# HFPB_01_PAGE-2.net
KiCad netlist of a schematic drawn in Altium Designer
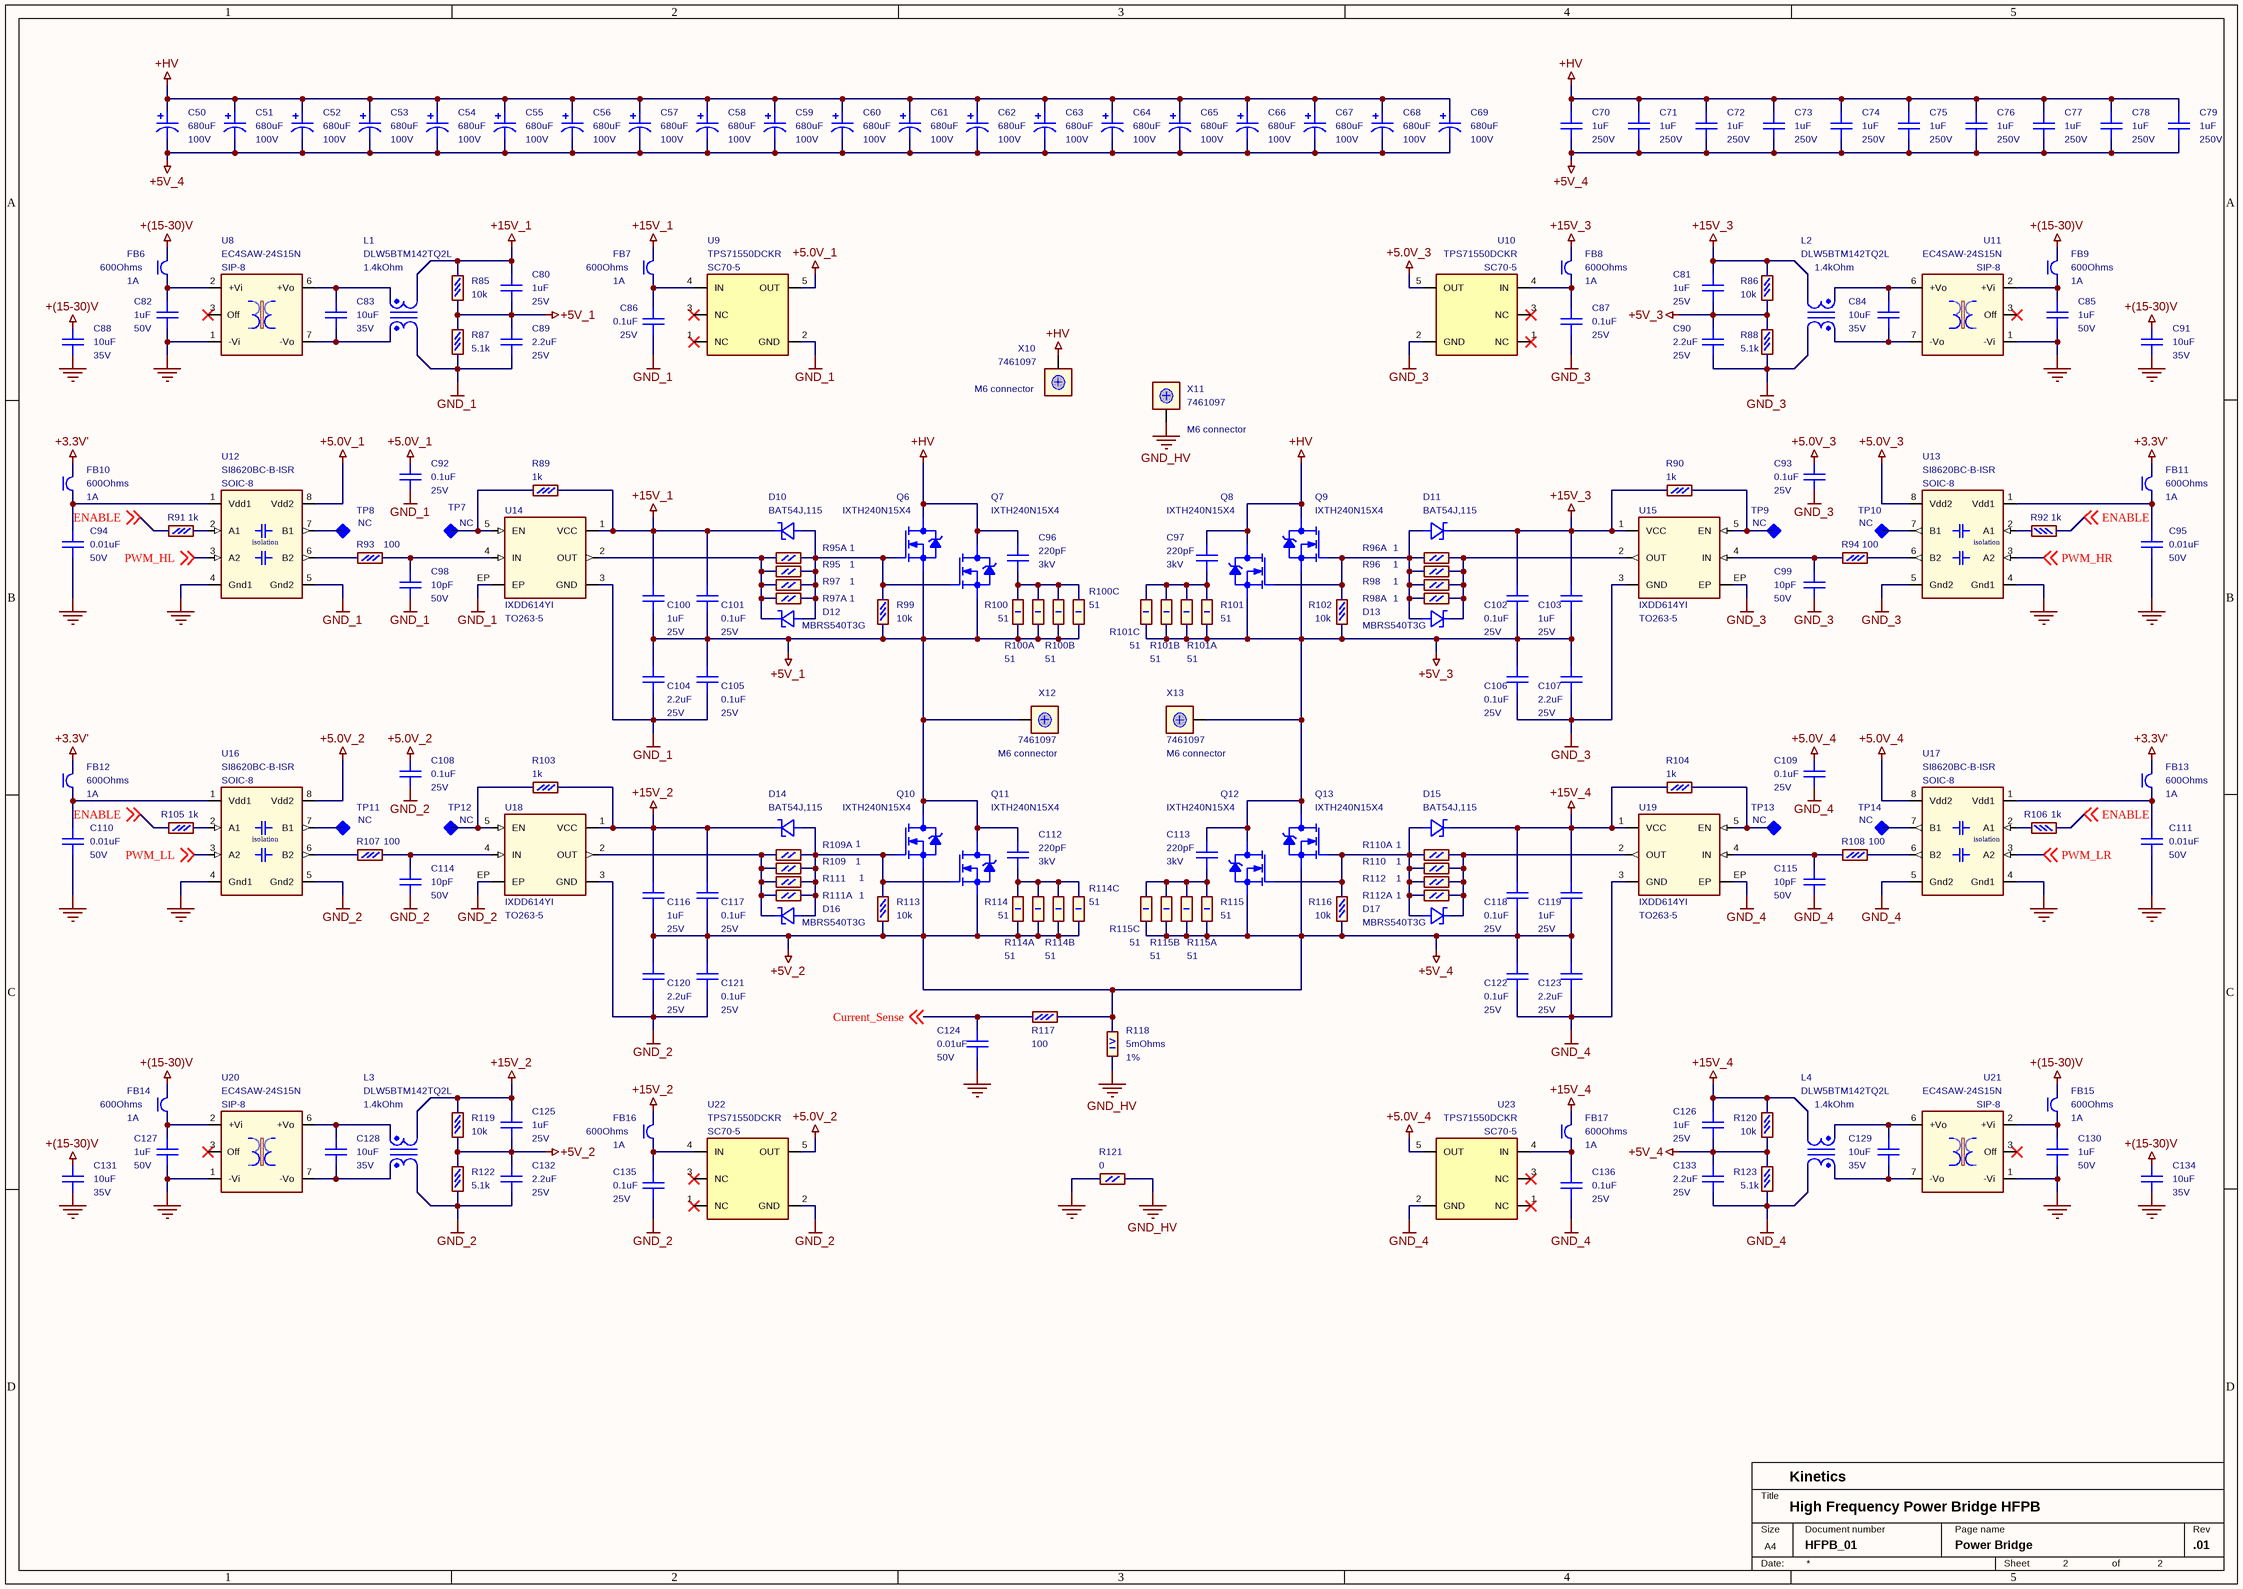
[diagram p0: HFPB_01, PAGE-2.SchDoc]

(export (version "E")
  (design (tool "Eeschema 10.0.6"))
  (components
    (comp (ref "C50")
      (value "680uF")
      (footprint "CAPPRD750W80D1820H4200")
      (description "Capacitor Aluminum Electrolytic Radial 680µF 100V 36mOhm")
      (fields
        (field (name "PART NUMBER") "EEU-FC2A681")
        (field (name "MANUFACTURER") "Panasonic")
        (field (name "VALUE3") "100V")
      )
      (libsource (lib "HFPB_01-SchLib") (part "EEU-FC2A681"))
    )
    (comp (ref "C51")
      (value "680uF")
      (footprint "CAPPRD750W80D1820H4200")
      (description "Capacitor Aluminum Electrolytic Radial 680µF 100V 36mOhm")
      (fields
        (field (name "PART NUMBER") "EEU-FC2A681")
        (field (name "MANUFACTURER") "Panasonic")
        (field (name "VALUE3") "100V")
      )
      (libsource (lib "HFPB_01-SchLib") (part "EEU-FC2A681"))
    )
    (comp (ref "C52")
      (value "680uF")
      (footprint "CAPPRD750W80D1820H4200")
      (description "Capacitor Aluminum Electrolytic Radial 680µF 100V 36mOhm")
      (fields
        (field (name "PART NUMBER") "EEU-FC2A681")
        (field (name "MANUFACTURER") "Panasonic")
        (field (name "VALUE3") "100V")
      )
      (libsource (lib "HFPB_01-SchLib") (part "EEU-FC2A681"))
    )
    (comp (ref "C53")
      (value "680uF")
      (footprint "CAPPRD750W80D1820H4200")
      (description "Capacitor Aluminum Electrolytic Radial 680µF 100V 36mOhm")
      (fields
        (field (name "PART NUMBER") "EEU-FC2A681")
        (field (name "MANUFACTURER") "Panasonic")
        (field (name "VALUE3") "100V")
      )
      (libsource (lib "HFPB_01-SchLib") (part "EEU-FC2A681"))
    )
    (comp (ref "C54")
      (value "680uF")
      (footprint "CAPPRD750W80D1820H4200")
      (description "Capacitor Aluminum Electrolytic Radial 680µF 100V 36mOhm")
      (fields
        (field (name "PART NUMBER") "EEU-FC2A681")
        (field (name "MANUFACTURER") "Panasonic")
        (field (name "VALUE3") "100V")
      )
      (libsource (lib "HFPB_01-SchLib") (part "EEU-FC2A681"))
    )
    (comp (ref "C55")
      (value "680uF")
      (footprint "CAPPRD750W80D1820H4200")
      (description "Capacitor Aluminum Electrolytic Radial 680µF 100V 36mOhm")
      (fields
        (field (name "PART NUMBER") "EEU-FC2A681")
        (field (name "MANUFACTURER") "Panasonic")
        (field (name "VALUE3") "100V")
      )
      (libsource (lib "HFPB_01-SchLib") (part "EEU-FC2A681"))
    )
    (comp (ref "C56")
      (value "680uF")
      (footprint "CAPPRD750W80D1820H4200")
      (description "Capacitor Aluminum Electrolytic Radial 680µF 100V 36mOhm")
      (fields
        (field (name "PART NUMBER") "EEU-FC2A681")
        (field (name "MANUFACTURER") "Panasonic")
        (field (name "VALUE3") "100V")
      )
      (libsource (lib "HFPB_01-SchLib") (part "EEU-FC2A681"))
    )
    (comp (ref "C57")
      (value "680uF")
      (footprint "CAPPRD750W80D1820H4200")
      (description "Capacitor Aluminum Electrolytic Radial 680µF 100V 36mOhm")
      (fields
        (field (name "PART NUMBER") "EEU-FC2A681")
        (field (name "MANUFACTURER") "Panasonic")
        (field (name "VALUE3") "100V")
      )
      (libsource (lib "HFPB_01-SchLib") (part "EEU-FC2A681"))
    )
    (comp (ref "C58")
      (value "680uF")
      (footprint "CAPPRD750W80D1820H4200")
      (description "Capacitor Aluminum Electrolytic Radial 680µF 100V 36mOhm")
      (fields
        (field (name "PART NUMBER") "EEU-FC2A681")
        (field (name "MANUFACTURER") "Panasonic")
        (field (name "VALUE3") "100V")
      )
      (libsource (lib "HFPB_01-SchLib") (part "EEU-FC2A681"))
    )
    (comp (ref "C59")
      (value "680uF")
      (footprint "CAPPRD750W80D1820H4200")
      (description "Capacitor Aluminum Electrolytic Radial 680µF 100V 36mOhm")
      (fields
        (field (name "PART NUMBER") "EEU-FC2A681")
        (field (name "MANUFACTURER") "Panasonic")
        (field (name "VALUE3") "100V")
      )
      (libsource (lib "HFPB_01-SchLib") (part "EEU-FC2A681"))
    )
    (comp (ref "C60")
      (value "680uF")
      (footprint "CAPPRD750W80D1820H4200")
      (description "Capacitor Aluminum Electrolytic Radial 680µF 100V 36mOhm")
      (fields
        (field (name "PART NUMBER") "EEU-FC2A681")
        (field (name "MANUFACTURER") "Panasonic")
        (field (name "VALUE3") "100V")
      )
      (libsource (lib "HFPB_01-SchLib") (part "EEU-FC2A681"))
    )
    (comp (ref "C61")
      (value "680uF")
      (footprint "CAPPRD750W80D1820H4200")
      (description "Capacitor Aluminum Electrolytic Radial 680µF 100V 36mOhm")
      (fields
        (field (name "PART NUMBER") "EEU-FC2A681")
        (field (name "MANUFACTURER") "Panasonic")
        (field (name "VALUE3") "100V")
      )
      (libsource (lib "HFPB_01-SchLib") (part "EEU-FC2A681"))
    )
    (comp (ref "C62")
      (value "680uF")
      (footprint "CAPPRD750W80D1820H4200")
      (description "Capacitor Aluminum Electrolytic Radial 680µF 100V 36mOhm")
      (fields
        (field (name "PART NUMBER") "EEU-FC2A681")
        (field (name "MANUFACTURER") "Panasonic")
        (field (name "VALUE3") "100V")
      )
      (libsource (lib "HFPB_01-SchLib") (part "EEU-FC2A681"))
    )
    (comp (ref "C63")
      (value "680uF")
      (footprint "CAPPRD750W80D1820H4200")
      (description "Capacitor Aluminum Electrolytic Radial 680µF 100V 36mOhm")
      (fields
        (field (name "PART NUMBER") "EEU-FC2A681")
        (field (name "MANUFACTURER") "Panasonic")
        (field (name "VALUE3") "100V")
      )
      (libsource (lib "HFPB_01-SchLib") (part "EEU-FC2A681"))
    )
    (comp (ref "C64")
      (value "680uF")
      (footprint "CAPPRD750W80D1820H4200")
      (description "Capacitor Aluminum Electrolytic Radial 680µF 100V 36mOhm")
      (fields
        (field (name "PART NUMBER") "EEU-FC2A681")
        (field (name "MANUFACTURER") "Panasonic")
        (field (name "VALUE3") "100V")
      )
      (libsource (lib "HFPB_01-SchLib") (part "EEU-FC2A681"))
    )
    (comp (ref "C65")
      (value "680uF")
      (footprint "CAPPRD750W80D1820H4200")
      (description "Capacitor Aluminum Electrolytic Radial 680µF 100V 36mOhm")
      (fields
        (field (name "PART NUMBER") "EEU-FC2A681")
        (field (name "MANUFACTURER") "Panasonic")
        (field (name "VALUE3") "100V")
      )
      (libsource (lib "HFPB_01-SchLib") (part "EEU-FC2A681"))
    )
    (comp (ref "C66")
      (value "680uF")
      (footprint "CAPPRD750W80D1820H4200")
      (description "Capacitor Aluminum Electrolytic Radial 680µF 100V 36mOhm")
      (fields
        (field (name "PART NUMBER") "EEU-FC2A681")
        (field (name "MANUFACTURER") "Panasonic")
        (field (name "VALUE3") "100V")
      )
      (libsource (lib "HFPB_01-SchLib") (part "EEU-FC2A681"))
    )
    (comp (ref "C67")
      (value "680uF")
      (footprint "CAPPRD750W80D1820H4200")
      (description "Capacitor Aluminum Electrolytic Radial 680µF 100V 36mOhm")
      (fields
        (field (name "PART NUMBER") "EEU-FC2A681")
        (field (name "MANUFACTURER") "Panasonic")
        (field (name "VALUE3") "100V")
      )
      (libsource (lib "HFPB_01-SchLib") (part "EEU-FC2A681"))
    )
    (comp (ref "C68")
      (value "680uF")
      (footprint "CAPPRD750W80D1820H4200")
      (description "Capacitor Aluminum Electrolytic Radial 680µF 100V 36mOhm")
      (fields
        (field (name "PART NUMBER") "EEU-FC2A681")
        (field (name "MANUFACTURER") "Panasonic")
        (field (name "VALUE3") "100V")
      )
      (libsource (lib "HFPB_01-SchLib") (part "EEU-FC2A681"))
    )
    (comp (ref "C69")
      (value "680uF")
      (footprint "CAPPRD750W80D1820H4200")
      (description "Capacitor Aluminum Electrolytic Radial 680µF 100V 36mOhm")
      (fields
        (field (name "PART NUMBER") "EEU-FC2A681")
        (field (name "MANUFACTURER") "Panasonic")
        (field (name "VALUE3") "100V")
      )
      (libsource (lib "HFPB_01-SchLib") (part "EEU-FC2A681"))
    )
    (comp (ref "C70")
      (value "1uF")
      (footprint "CAPC570X500X160L60N")
      (description "Capacitor 2220")
      (fields
        (field (name "PART NUMBER") "C2220C105KARACTU")
        (field (name "MANUFACTURER") "KEMET")
        (field (name "VALUE3") "250V")
      )
      (libsource (lib "HFPB_01-SchLib") (part "C2220"))
    )
    (comp (ref "C71")
      (value "1uF")
      (footprint "CAPC570X500X160L60N")
      (description "Capacitor 2220")
      (fields
        (field (name "PART NUMBER") "C2220C105KARACTU")
        (field (name "MANUFACTURER") "KEMET")
        (field (name "VALUE3") "250V")
      )
      (libsource (lib "HFPB_01-SchLib") (part "C2220"))
    )
    (comp (ref "C72")
      (value "1uF")
      (footprint "CAPC570X500X160L60N")
      (description "Capacitor 2220")
      (fields
        (field (name "PART NUMBER") "C2220C105KARACTU")
        (field (name "MANUFACTURER") "KEMET")
        (field (name "VALUE3") "250V")
      )
      (libsource (lib "HFPB_01-SchLib") (part "C2220"))
    )
    (comp (ref "C73")
      (value "1uF")
      (footprint "CAPC570X500X160L60N")
      (description "Capacitor 2220")
      (fields
        (field (name "PART NUMBER") "C2220C105KARACTU")
        (field (name "MANUFACTURER") "KEMET")
        (field (name "VALUE3") "250V")
      )
      (libsource (lib "HFPB_01-SchLib") (part "C2220"))
    )
    (comp (ref "C74")
      (value "1uF")
      (footprint "CAPC570X500X160L60N")
      (description "Capacitor 2220")
      (fields
        (field (name "PART NUMBER") "C2220C105KARACTU")
        (field (name "MANUFACTURER") "KEMET")
        (field (name "VALUE3") "250V")
      )
      (libsource (lib "HFPB_01-SchLib") (part "C2220"))
    )
    (comp (ref "C75")
      (value "1uF")
      (footprint "CAPC570X500X160L60N")
      (description "Capacitor 2220")
      (fields
        (field (name "PART NUMBER") "C2220C105KARACTU")
        (field (name "MANUFACTURER") "KEMET")
        (field (name "VALUE3") "250V")
      )
      (libsource (lib "HFPB_01-SchLib") (part "C2220"))
    )
    (comp (ref "C76")
      (value "1uF")
      (footprint "CAPC570X500X160L60N")
      (description "Capacitor 2220")
      (fields
        (field (name "PART NUMBER") "C2220C105KARACTU")
        (field (name "MANUFACTURER") "KEMET")
        (field (name "VALUE3") "250V")
      )
      (libsource (lib "HFPB_01-SchLib") (part "C2220"))
    )
    (comp (ref "C77")
      (value "1uF")
      (footprint "CAPC570X500X160L60N")
      (description "Capacitor 2220")
      (fields
        (field (name "PART NUMBER") "C2220C105KARACTU")
        (field (name "MANUFACTURER") "KEMET")
        (field (name "VALUE3") "250V")
      )
      (libsource (lib "HFPB_01-SchLib") (part "C2220"))
    )
    (comp (ref "C78")
      (value "1uF")
      (footprint "CAPC570X500X160L60N")
      (description "Capacitor 2220")
      (fields
        (field (name "PART NUMBER") "C2220C105KARACTU")
        (field (name "MANUFACTURER") "KEMET")
        (field (name "VALUE3") "250V")
      )
      (libsource (lib "HFPB_01-SchLib") (part "C2220"))
    )
    (comp (ref "C79")
      (value "1uF")
      (footprint "CAPC570X500X160L60N")
      (description "Capacitor 2220")
      (fields
        (field (name "PART NUMBER") "C2220C105KARACTU")
        (field (name "MANUFACTURER") "KEMET")
        (field (name "VALUE3") "250V")
      )
      (libsource (lib "HFPB_01-SchLib") (part "C2220"))
    )
    (comp (ref "C80")
      (value "1uF")
      (footprint "CAPC160X80X80L35N - Full legend")
      (description "Capacitor 0603")
      (fields
        (field (name "PART NUMBER") "C1608X7R1E105K080AB")
        (field (name "MANUFACTURER") "TDK")
        (field (name "VALUE3") "25V")
      )
      (libsource (lib "HFPB_01-SchLib") (part "C0603"))
    )
    (comp (ref "C81")
      (value "1uF")
      (footprint "CAPC160X80X80L35N - Full legend")
      (description "Capacitor 0603")
      (fields
        (field (name "PART NUMBER") "C1608X7R1E105K080AB")
        (field (name "MANUFACTURER") "TDK")
        (field (name "VALUE3") "25V")
      )
      (libsource (lib "HFPB_01-SchLib") (part "C0603"))
    )
    (comp (ref "C82")
      (value "1uF")
      (footprint "CAPC160X80X80L35N - Full legend")
      (description "Capacitor 0603")
      (fields
        (field (name "PART NUMBER") "GRT188R61H105KE13D")
        (field (name "MANUFACTURER") "Murata")
        (field (name "VALUE3") "50V")
      )
      (libsource (lib "HFPB_01-SchLib") (part "C0603"))
    )
    (comp (ref "C83")
      (value "10uF")
      (footprint "CAPC320X250X280L60N - full legend")
      (description "Capacitor 1210")
      (fields
        (field (name "PART NUMBER") "C1210C106M6PACTU")
        (field (name "MANUFACTURER") "KEMET")
        (field (name "VALUE3") "35V")
      )
      (libsource (lib "HFPB_01-SchLib") (part "C1210"))
    )
    (comp (ref "C84")
      (value "10uF")
      (footprint "CAPC320X250X280L60N - full legend")
      (description "Capacitor 1210")
      (fields
        (field (name "PART NUMBER") "C1210C106M6PACTU")
        (field (name "MANUFACTURER") "KEMET")
        (field (name "VALUE3") "35V")
      )
      (libsource (lib "HFPB_01-SchLib") (part "C1210"))
    )
    (comp (ref "C85")
      (value "1uF")
      (footprint "CAPC160X80X80L35N - Full legend")
      (description "Capacitor 0603")
      (fields
        (field (name "PART NUMBER") "GRT188R61H105KE13D")
        (field (name "MANUFACTURER") "Murata")
        (field (name "VALUE3") "50V")
      )
      (libsource (lib "HFPB_01-SchLib") (part "C0603"))
    )
    (comp (ref "C86")
      (value "0.1uF")
      (footprint "CAPC160X80X80L35N - Full legend")
      (description "Capacitor 0603")
      (fields
        (field (name "PART NUMBER") "C0603C104K3RAC7082")
        (field (name "MANUFACTURER") "KEMET")
        (field (name "VALUE3") "25V")
      )
      (libsource (lib "HFPB_01-SchLib") (part "C0603"))
    )
    (comp (ref "C87")
      (value "0.1uF")
      (footprint "CAPC160X80X80L35N - Full legend")
      (description "Capacitor 0603")
      (fields
        (field (name "PART NUMBER") "C0603C104K3RAC7082")
        (field (name "MANUFACTURER") "KEMET")
        (field (name "VALUE3") "25V")
      )
      (libsource (lib "HFPB_01-SchLib") (part "C0603"))
    )
    (comp (ref "C88")
      (value "10uF")
      (footprint "CAPC320X250X280L60N - full legend")
      (description "Capacitor 1210")
      (fields
        (field (name "PART NUMBER") "C1210C106M6PACTU")
        (field (name "MANUFACTURER") "KEMET")
        (field (name "VALUE3") "35V")
      )
      (libsource (lib "HFPB_01-SchLib") (part "C1210"))
    )
    (comp (ref "C89")
      (value "2.2uF")
      (footprint "CAPC160X80X80L35N - Full legend")
      (description "Capacitor 0603")
      (fields
        (field (name "PART NUMBER") "C1608X5R1E225K080AB")
        (field (name "MANUFACTURER") "TDK")
        (field (name "VALUE3") "25V")
      )
      (libsource (lib "HFPB_01-SchLib") (part "C0603"))
    )
    (comp (ref "C90")
      (value "2.2uF")
      (footprint "CAPC160X80X80L35N - Full legend")
      (description "Capacitor 0603")
      (fields
        (field (name "PART NUMBER") "C1608X5R1E225K080AB")
        (field (name "MANUFACTURER") "TDK")
        (field (name "VALUE3") "25V")
      )
      (libsource (lib "HFPB_01-SchLib") (part "C0603"))
    )
    (comp (ref "C91")
      (value "10uF")
      (footprint "CAPC320X250X280L60N - full legend")
      (description "Capacitor 1210")
      (fields
        (field (name "PART NUMBER") "C1210C106M6PACTU")
        (field (name "MANUFACTURER") "KEMET")
        (field (name "VALUE3") "35V")
      )
      (libsource (lib "HFPB_01-SchLib") (part "C1210"))
    )
    (comp (ref "C92")
      (value "0.1uF")
      (footprint "CAPC160X80X80L35N - Full legend")
      (description "Capacitor 0603")
      (fields
        (field (name "PART NUMBER") "C0603C104K3RAC7082")
        (field (name "MANUFACTURER") "KEMET")
        (field (name "VALUE3") "25V")
      )
      (libsource (lib "HFPB_01-SchLib") (part "C0603"))
    )
    (comp (ref "C93")
      (value "0.1uF")
      (footprint "CAPC160X80X80L35N - Full legend")
      (description "Capacitor 0603")
      (fields
        (field (name "PART NUMBER") "C0603C104K3RAC7082")
        (field (name "MANUFACTURER") "KEMET")
        (field (name "VALUE3") "25V")
      )
      (libsource (lib "HFPB_01-SchLib") (part "C0603"))
    )
    (comp (ref "C94")
      (value "0.01uF")
      (footprint "CAPC160X80X80L35N - Full legend")
      (description "Capacitor 0603")
      (fields
        (field (name "PART NUMBER") "GRM1885C1H103JA01D")
        (field (name "MANUFACTURER") "Murata")
        (field (name "VALUE3") "50V")
      )
      (libsource (lib "HFPB_01-SchLib") (part "C0603"))
    )
    (comp (ref "C95")
      (value "0.01uF")
      (footprint "CAPC160X80X80L35N - Full legend")
      (description "Capacitor 0603")
      (fields
        (field (name "PART NUMBER") "GRM1885C1H103JA01D")
        (field (name "MANUFACTURER") "Murata")
        (field (name "VALUE3") "50V")
      )
      (libsource (lib "HFPB_01-SchLib") (part "C0603"))
    )
    (comp (ref "C96")
      (value "220pF")
      (footprint "CAPC450X320X140L60N")
      (description "Capacitor 1812")
      (fields
        (field (name "PART NUMBER") "CGA8M1C0G3F221K200KA")
        (field (name "MANUFACTURER") "TDK")
        (field (name "VALUE3") "3kV")
      )
      (libsource (lib "HFPB_01-SchLib") (part "C1812"))
    )
    (comp (ref "C97")
      (value "220pF")
      (footprint "CAPC450X320X140L60N")
      (description "Capacitor 1812")
      (fields
        (field (name "PART NUMBER") "CGA8M1C0G3F221K200KA")
        (field (name "MANUFACTURER") "TDK")
        (field (name "VALUE3") "3kV")
      )
      (libsource (lib "HFPB_01-SchLib") (part "C1812"))
    )
    (comp (ref "C98")
      (value "10pF")
      (footprint "CAPC160X80X80L35N - Full legend")
      (description "Capacitor 0603")
      (fields
        (field (name "PART NUMBER") "GRM1885C1H100JA01D")
        (field (name "MANUFACTURER") "Murata")
        (field (name "VALUE3") "50V")
      )
      (libsource (lib "HFPB_01-SchLib") (part "C0603"))
    )
    (comp (ref "C99")
      (value "10pF")
      (footprint "CAPC160X80X80L35N - Full legend")
      (description "Capacitor 0603")
      (fields
        (field (name "PART NUMBER") "GRM1885C1H100JA01D")
        (field (name "MANUFACTURER") "Murata")
        (field (name "VALUE3") "50V")
      )
      (libsource (lib "HFPB_01-SchLib") (part "C0603"))
    )
    (comp (ref "C100")
      (value "1uF")
      (footprint "CAPC160X80X80L35N - Full legend")
      (description "Capacitor 0603")
      (fields
        (field (name "PART NUMBER") "C1608X7R1E105K080AB")
        (field (name "MANUFACTURER") "TDK")
        (field (name "VALUE3") "25V")
      )
      (libsource (lib "HFPB_01-SchLib") (part "C0603"))
    )
    (comp (ref "C101")
      (value "0.1uF")
      (footprint "CAPC160X80X80L35N - Full legend")
      (description "Capacitor 0603")
      (fields
        (field (name "PART NUMBER") "C0603C104K3RAC7082")
        (field (name "MANUFACTURER") "KEMET")
        (field (name "VALUE3") "25V")
      )
      (libsource (lib "HFPB_01-SchLib") (part "C0603"))
    )
    (comp (ref "C102")
      (value "0.1uF")
      (footprint "CAPC160X80X80L35N - Full legend")
      (description "Capacitor 0603")
      (fields
        (field (name "PART NUMBER") "C0603C104K3RAC7082")
        (field (name "MANUFACTURER") "KEMET")
        (field (name "VALUE3") "25V")
      )
      (libsource (lib "HFPB_01-SchLib") (part "C0603"))
    )
    (comp (ref "C103")
      (value "1uF")
      (footprint "CAPC160X80X80L35N - Full legend")
      (description "Capacitor 0603")
      (fields
        (field (name "PART NUMBER") "C1608X7R1E105K080AB")
        (field (name "MANUFACTURER") "TDK")
        (field (name "VALUE3") "25V")
      )
      (libsource (lib "HFPB_01-SchLib") (part "C0603"))
    )
    (comp (ref "C104")
      (value "2.2uF")
      (footprint "CAPC160X80X80L35N - Full legend")
      (description "Capacitor 0603")
      (fields
        (field (name "PART NUMBER") "C1608X5R1E225K080AB")
        (field (name "MANUFACTURER") "TDK")
        (field (name "VALUE3") "25V")
      )
      (libsource (lib "HFPB_01-SchLib") (part "C0603"))
    )
    (comp (ref "C105")
      (value "0.1uF")
      (footprint "CAPC160X80X80L35N - Full legend")
      (description "Capacitor 0603")
      (fields
        (field (name "PART NUMBER") "C0603C104K3RAC7082")
        (field (name "MANUFACTURER") "KEMET")
        (field (name "VALUE3") "25V")
      )
      (libsource (lib "HFPB_01-SchLib") (part "C0603"))
    )
    (comp (ref "C106")
      (value "0.1uF")
      (footprint "CAPC160X80X80L35N - Full legend")
      (description "Capacitor 0603")
      (fields
        (field (name "PART NUMBER") "C0603C104K3RAC7082")
        (field (name "MANUFACTURER") "KEMET")
        (field (name "VALUE3") "25V")
      )
      (libsource (lib "HFPB_01-SchLib") (part "C0603"))
    )
    (comp (ref "C107")
      (value "2.2uF")
      (footprint "CAPC160X80X80L35N - Full legend")
      (description "Capacitor 0603")
      (fields
        (field (name "PART NUMBER") "C1608X5R1E225K080AB")
        (field (name "MANUFACTURER") "TDK")
        (field (name "VALUE3") "25V")
      )
      (libsource (lib "HFPB_01-SchLib") (part "C0603"))
    )
    (comp (ref "C108")
      (value "0.1uF")
      (footprint "CAPC160X80X80L35N - Full legend")
      (description "Capacitor 0603")
      (fields
        (field (name "PART NUMBER") "C0603C104K3RAC7082")
        (field (name "MANUFACTURER") "KEMET")
        (field (name "VALUE3") "25V")
      )
      (libsource (lib "HFPB_01-SchLib") (part "C0603"))
    )
    (comp (ref "C109")
      (value "0.1uF")
      (footprint "CAPC160X80X80L35N - Full legend")
      (description "Capacitor 0603")
      (fields
        (field (name "PART NUMBER") "C0603C104K3RAC7082")
        (field (name "MANUFACTURER") "KEMET")
        (field (name "VALUE3") "25V")
      )
      (libsource (lib "HFPB_01-SchLib") (part "C0603"))
    )
    (comp (ref "C110")
      (value "0.01uF")
      (footprint "CAPC160X80X80L35N - Full legend")
      (description "Capacitor 0603")
      (fields
        (field (name "PART NUMBER") "GRM1885C1H103JA01D")
        (field (name "MANUFACTURER") "Murata")
        (field (name "VALUE3") "50V")
      )
      (libsource (lib "HFPB_01-SchLib") (part "C0603"))
    )
    (comp (ref "C111")
      (value "0.01uF")
      (footprint "CAPC160X80X80L35N - Full legend")
      (description "Capacitor 0603")
      (fields
        (field (name "PART NUMBER") "GRM1885C1H103JA01D")
        (field (name "MANUFACTURER") "Murata")
        (field (name "VALUE3") "50V")
      )
      (libsource (lib "HFPB_01-SchLib") (part "C0603"))
    )
    (comp (ref "C112")
      (value "220pF")
      (footprint "CAPC450X320X140L60N")
      (description "Capacitor 1812")
      (fields
        (field (name "PART NUMBER") "CGA8M1C0G3F221K200KA")
        (field (name "MANUFACTURER") "TDK")
        (field (name "VALUE3") "3kV")
      )
      (libsource (lib "HFPB_01-SchLib") (part "C1812"))
    )
    (comp (ref "C113")
      (value "220pF")
      (footprint "CAPC450X320X140L60N")
      (description "Capacitor 1812")
      (fields
        (field (name "PART NUMBER") "CGA8M1C0G3F221K200KA")
        (field (name "MANUFACTURER") "TDK")
        (field (name "VALUE3") "3kV")
      )
      (libsource (lib "HFPB_01-SchLib") (part "C1812"))
    )
    (comp (ref "C114")
      (value "10pF")
      (footprint "CAPC160X80X80L35N - Full legend")
      (description "Capacitor 0603")
      (fields
        (field (name "PART NUMBER") "GRM1885C1H100JA01D")
        (field (name "MANUFACTURER") "Murata")
        (field (name "VALUE3") "50V")
      )
      (libsource (lib "HFPB_01-SchLib") (part "C0603"))
    )
    (comp (ref "C115")
      (value "10pF")
      (footprint "CAPC160X80X80L35N - Full legend")
      (description "Capacitor 0603")
      (fields
        (field (name "PART NUMBER") "GRM1885C1H100JA01D")
        (field (name "MANUFACTURER") "Murata")
        (field (name "VALUE3") "50V")
      )
      (libsource (lib "HFPB_01-SchLib") (part "C0603"))
    )
    (comp (ref "C116")
      (value "1uF")
      (footprint "CAPC160X80X80L35N - Full legend")
      (description "Capacitor 0603")
      (fields
        (field (name "PART NUMBER") "C1608X7R1E105K080AB")
        (field (name "MANUFACTURER") "TDK")
        (field (name "VALUE3") "25V")
      )
      (libsource (lib "HFPB_01-SchLib") (part "C0603"))
    )
    (comp (ref "C117")
      (value "0.1uF")
      (footprint "CAPC160X80X80L35N - Full legend")
      (description "Capacitor 0603")
      (fields
        (field (name "PART NUMBER") "C0603C104K3RAC7082")
        (field (name "MANUFACTURER") "KEMET")
        (field (name "VALUE3") "25V")
      )
      (libsource (lib "HFPB_01-SchLib") (part "C0603"))
    )
    (comp (ref "C118")
      (value "0.1uF")
      (footprint "CAPC160X80X80L35N - Full legend")
      (description "Capacitor 0603")
      (fields
        (field (name "PART NUMBER") "C0603C104K3RAC7082")
        (field (name "MANUFACTURER") "KEMET")
        (field (name "VALUE3") "25V")
      )
      (libsource (lib "HFPB_01-SchLib") (part "C0603"))
    )
    (comp (ref "C119")
      (value "1uF")
      (footprint "CAPC160X80X80L35N - Full legend")
      (description "Capacitor 0603")
      (fields
        (field (name "PART NUMBER") "C1608X7R1E105K080AB")
        (field (name "MANUFACTURER") "TDK")
        (field (name "VALUE3") "25V")
      )
      (libsource (lib "HFPB_01-SchLib") (part "C0603"))
    )
    (comp (ref "C120")
      (value "2.2uF")
      (footprint "CAPC160X80X80L35N - Full legend")
      (description "Capacitor 0603")
      (fields
        (field (name "PART NUMBER") "C1608X5R1E225K080AB")
        (field (name "MANUFACTURER") "TDK")
        (field (name "VALUE3") "25V")
      )
      (libsource (lib "HFPB_01-SchLib") (part "C0603"))
    )
    (comp (ref "C121")
      (value "0.1uF")
      (footprint "CAPC160X80X80L35N - Full legend")
      (description "Capacitor 0603")
      (fields
        (field (name "PART NUMBER") "C0603C104K3RAC7082")
        (field (name "MANUFACTURER") "KEMET")
        (field (name "VALUE3") "25V")
      )
      (libsource (lib "HFPB_01-SchLib") (part "C0603"))
    )
    (comp (ref "C122")
      (value "0.1uF")
      (footprint "CAPC160X80X80L35N - Full legend")
      (description "Capacitor 0603")
      (fields
        (field (name "PART NUMBER") "C0603C104K3RAC7082")
        (field (name "MANUFACTURER") "KEMET")
        (field (name "VALUE3") "25V")
      )
      (libsource (lib "HFPB_01-SchLib") (part "C0603"))
    )
    (comp (ref "C123")
      (value "2.2uF")
      (footprint "CAPC160X80X80L35N - Full legend")
      (description "Capacitor 0603")
      (fields
        (field (name "PART NUMBER") "C1608X5R1E225K080AB")
        (field (name "MANUFACTURER") "TDK")
        (field (name "VALUE3") "25V")
      )
      (libsource (lib "HFPB_01-SchLib") (part "C0603"))
    )
    (comp (ref "C124")
      (value "0.01uF")
      (footprint "CAPC160X80X80L35N - Full legend")
      (description "Capacitor 0603")
      (fields
        (field (name "PART NUMBER") "GRM1885C1H103JA01D")
        (field (name "MANUFACTURER") "Murata")
        (field (name "VALUE3") "50V")
      )
      (libsource (lib "HFPB_01-SchLib") (part "C0603"))
    )
    (comp (ref "C125")
      (value "1uF")
      (footprint "CAPC160X80X80L35N - Full legend")
      (description "Capacitor 0603")
      (fields
        (field (name "PART NUMBER") "C1608X7R1E105K080AB")
        (field (name "MANUFACTURER") "TDK")
        (field (name "VALUE3") "25V")
      )
      (libsource (lib "HFPB_01-SchLib") (part "C0603"))
    )
    (comp (ref "C126")
      (value "1uF")
      (footprint "CAPC160X80X80L35N - Full legend")
      (description "Capacitor 0603")
      (fields
        (field (name "PART NUMBER") "C1608X7R1E105K080AB")
        (field (name "MANUFACTURER") "TDK")
        (field (name "VALUE3") "25V")
      )
      (libsource (lib "HFPB_01-SchLib") (part "C0603"))
    )
    (comp (ref "C127")
      (value "1uF")
      (footprint "CAPC160X80X80L35N - Full legend")
      (description "Capacitor 0603")
      (fields
        (field (name "PART NUMBER") "GRT188R61H105KE13D")
        (field (name "MANUFACTURER") "Murata")
        (field (name "VALUE3") "50V")
      )
      (libsource (lib "HFPB_01-SchLib") (part "C0603"))
    )
    (comp (ref "C128")
      (value "10uF")
      (footprint "CAPC320X250X280L60N - full legend")
      (description "Capacitor 1210")
      (fields
        (field (name "PART NUMBER") "C1210C106M6PACTU")
        (field (name "MANUFACTURER") "KEMET")
        (field (name "VALUE3") "35V")
      )
      (libsource (lib "HFPB_01-SchLib") (part "C1210"))
    )
    (comp (ref "C129")
      (value "10uF")
      (footprint "CAPC320X250X280L60N - full legend")
      (description "Capacitor 1210")
      (fields
        (field (name "PART NUMBER") "C1210C106M6PACTU")
        (field (name "MANUFACTURER") "KEMET")
        (field (name "VALUE3") "35V")
      )
      (libsource (lib "HFPB_01-SchLib") (part "C1210"))
    )
    (comp (ref "C130")
      (value "1uF")
      (footprint "CAPC160X80X80L35N - Full legend")
      (description "Capacitor 0603")
      (fields
        (field (name "PART NUMBER") "GRT188R61H105KE13D")
        (field (name "MANUFACTURER") "Murata")
        (field (name "VALUE3") "50V")
      )
      (libsource (lib "HFPB_01-SchLib") (part "C0603"))
    )
    (comp (ref "C131")
      (value "10uF")
      (footprint "CAPC320X250X280L60N - full legend")
      (description "Capacitor 1210")
      (fields
        (field (name "PART NUMBER") "C1210C106M6PACTU")
        (field (name "MANUFACTURER") "KEMET")
        (field (name "VALUE3") "35V")
      )
      (libsource (lib "HFPB_01-SchLib") (part "C1210"))
    )
    (comp (ref "C132")
      (value "2.2uF")
      (footprint "CAPC160X80X80L35N - Full legend")
      (description "Capacitor 0603")
      (fields
        (field (name "PART NUMBER") "C1608X5R1E225K080AB")
        (field (name "MANUFACTURER") "TDK")
        (field (name "VALUE3") "25V")
      )
      (libsource (lib "HFPB_01-SchLib") (part "C0603"))
    )
    (comp (ref "C133")
      (value "2.2uF")
      (footprint "CAPC160X80X80L35N - Full legend")
      (description "Capacitor 0603")
      (fields
        (field (name "PART NUMBER") "C1608X5R1E225K080AB")
        (field (name "MANUFACTURER") "TDK")
        (field (name "VALUE3") "25V")
      )
      (libsource (lib "HFPB_01-SchLib") (part "C0603"))
    )
    (comp (ref "C134")
      (value "10uF")
      (footprint "CAPC320X250X280L60N - full legend")
      (description "Capacitor 1210")
      (fields
        (field (name "PART NUMBER") "C1210C106M6PACTU")
        (field (name "MANUFACTURER") "KEMET")
        (field (name "VALUE3") "35V")
      )
      (libsource (lib "HFPB_01-SchLib") (part "C1210"))
    )
    (comp (ref "C135")
      (value "0.1uF")
      (footprint "CAPC160X80X80L35N - Full legend")
      (description "Capacitor 0603")
      (fields
        (field (name "PART NUMBER") "C0603C104K3RAC7082")
        (field (name "MANUFACTURER") "KEMET")
        (field (name "VALUE3") "25V")
      )
      (libsource (lib "HFPB_01-SchLib") (part "C0603"))
    )
    (comp (ref "C136")
      (value "0.1uF")
      (footprint "CAPC160X80X80L35N - Full legend")
      (description "Capacitor 0603")
      (fields
        (field (name "PART NUMBER") "C0603C104K3RAC7082")
        (field (name "MANUFACTURER") "KEMET")
        (field (name "VALUE3") "25V")
      )
      (libsource (lib "HFPB_01-SchLib") (part "C0603"))
    )
    (comp (ref "D10")
      (value "BAT54J,115")
      (footprint "SODFL250X125X80L40X32N")
      (description "Diode Schottky 30V 0.2A")
      (fields (field (name "MANUFACTURER") "Nexperia"))
      (libsource (lib "HFPB_01-SchLib") (part "BAT54J,115"))
    )
    (comp (ref "D11")
      (value "BAT54J,115")
      (footprint "SODFL250X125X80L40X32N")
      (description "Diode Schottky 30V 0.2A")
      (fields (field (name "MANUFACTURER") "Nexperia"))
      (libsource (lib "HFPB_01-SchLib") (part "BAT54J,115"))
    )
    (comp (ref "D12")
      (value "MBRS540T3G")
      (footprint "DIOM795X585X240L100X300N")
      (description "Diode Schottky 40V 5A")
      (fields (field (name "MANUFACTURER") "ON Semiconductor"))
      (libsource (lib "HFPB_01-SchLib") (part "MBRS540T3G"))
    )
    (comp (ref "D13")
      (value "MBRS540T3G")
      (footprint "DIOM795X585X240L100X300N")
      (description "Diode Schottky 40V 5A")
      (fields (field (name "MANUFACTURER") "ON Semiconductor"))
      (libsource (lib "HFPB_01-SchLib") (part "MBRS540T3G"))
    )
    (comp (ref "D14")
      (value "BAT54J,115")
      (footprint "SODFL250X125X80L40X32N")
      (description "Diode Schottky 30V 0.2A")
      (fields (field (name "MANUFACTURER") "Nexperia"))
      (libsource (lib "HFPB_01-SchLib") (part "BAT54J,115"))
    )
    (comp (ref "D15")
      (value "BAT54J,115")
      (footprint "SODFL250X125X80L40X32N")
      (description "Diode Schottky 30V 0.2A")
      (fields (field (name "MANUFACTURER") "Nexperia"))
      (libsource (lib "HFPB_01-SchLib") (part "BAT54J,115"))
    )
    (comp (ref "D16")
      (value "MBRS540T3G")
      (footprint "DIOM795X585X240L100X300N")
      (description "Diode Schottky 40V 5A")
      (fields (field (name "MANUFACTURER") "ON Semiconductor"))
      (libsource (lib "HFPB_01-SchLib") (part "MBRS540T3G"))
    )
    (comp (ref "D17")
      (value "MBRS540T3G")
      (footprint "DIOM795X585X240L100X300N")
      (description "Diode Schottky 40V 5A")
      (fields (field (name "MANUFACTURER") "ON Semiconductor"))
      (libsource (lib "HFPB_01-SchLib") (part "MBRS540T3G"))
    )
    (comp (ref "FB6")
      (value "600Ohms")
      (footprint "BEADC160X80X80L30N")
      (description "Ferrite Bead 600Ohms 1A")
      (fields
        (field (name "PART NUMBER") "MPZ1608S601ATA00")
        (field (name "MANUFACTURER") "TDK")
        (field (name "VALUE1") "1A")
      )
      (libsource (lib "HFPB_01-SchLib") (part "MPZ1608S601ATA00"))
    )
    (comp (ref "FB7")
      (value "600Ohms")
      (footprint "BEADC160X80X80L30N")
      (description "Ferrite Bead 600Ohms 1A")
      (fields
        (field (name "PART NUMBER") "MPZ1608S601ATA00")
        (field (name "MANUFACTURER") "TDK")
        (field (name "VALUE1") "1A")
      )
      (libsource (lib "HFPB_01-SchLib") (part "MPZ1608S601ATA00"))
    )
    (comp (ref "FB8")
      (value "600Ohms")
      (footprint "BEADC160X80X80L30N")
      (description "Ferrite Bead 600Ohms 1A")
      (fields
        (field (name "PART NUMBER") "MPZ1608S601ATA00")
        (field (name "MANUFACTURER") "TDK")
        (field (name "VALUE1") "1A")
      )
      (libsource (lib "HFPB_01-SchLib") (part "MPZ1608S601ATA00"))
    )
    (comp (ref "FB9")
      (value "600Ohms")
      (footprint "BEADC160X80X80L30N")
      (description "Ferrite Bead 600Ohms 1A")
      (fields
        (field (name "PART NUMBER") "MPZ1608S601ATA00")
        (field (name "MANUFACTURER") "TDK")
        (field (name "VALUE1") "1A")
      )
      (libsource (lib "HFPB_01-SchLib") (part "MPZ1608S601ATA00"))
    )
    (comp (ref "FB10")
      (value "600Ohms")
      (footprint "BEADC160X80X80L30N")
      (description "Ferrite Bead 600Ohms 1A")
      (fields
        (field (name "PART NUMBER") "MPZ1608S601ATA00")
        (field (name "MANUFACTURER") "TDK")
        (field (name "VALUE1") "1A")
      )
      (libsource (lib "HFPB_01-SchLib") (part "MPZ1608S601ATA00"))
    )
    (comp (ref "FB11")
      (value "600Ohms")
      (footprint "BEADC160X80X80L30N")
      (description "Ferrite Bead 600Ohms 1A")
      (fields
        (field (name "PART NUMBER") "MPZ1608S601ATA00")
        (field (name "MANUFACTURER") "TDK")
        (field (name "VALUE1") "1A")
      )
      (libsource (lib "HFPB_01-SchLib") (part "MPZ1608S601ATA00"))
    )
    (comp (ref "FB12")
      (value "600Ohms")
      (footprint "BEADC160X80X80L30N")
      (description "Ferrite Bead 600Ohms 1A")
      (fields
        (field (name "PART NUMBER") "MPZ1608S601ATA00")
        (field (name "MANUFACTURER") "TDK")
        (field (name "VALUE1") "1A")
      )
      (libsource (lib "HFPB_01-SchLib") (part "MPZ1608S601ATA00"))
    )
    (comp (ref "FB13")
      (value "600Ohms")
      (footprint "BEADC160X80X80L30N")
      (description "Ferrite Bead 600Ohms 1A")
      (fields
        (field (name "PART NUMBER") "MPZ1608S601ATA00")
        (field (name "MANUFACTURER") "TDK")
        (field (name "VALUE1") "1A")
      )
      (libsource (lib "HFPB_01-SchLib") (part "MPZ1608S601ATA00"))
    )
    (comp (ref "FB14")
      (value "600Ohms")
      (footprint "BEADC160X80X80L30N")
      (description "Ferrite Bead 600Ohms 1A")
      (fields
        (field (name "PART NUMBER") "MPZ1608S601ATA00")
        (field (name "MANUFACTURER") "TDK")
        (field (name "VALUE1") "1A")
      )
      (libsource (lib "HFPB_01-SchLib") (part "MPZ1608S601ATA00"))
    )
    (comp (ref "FB15")
      (value "600Ohms")
      (footprint "BEADC160X80X80L30N")
      (description "Ferrite Bead 600Ohms 1A")
      (fields
        (field (name "PART NUMBER") "MPZ1608S601ATA00")
        (field (name "MANUFACTURER") "TDK")
        (field (name "VALUE1") "1A")
      )
      (libsource (lib "HFPB_01-SchLib") (part "MPZ1608S601ATA00"))
    )
    (comp (ref "FB16")
      (value "600Ohms")
      (footprint "BEADC160X80X80L30N")
      (description "Ferrite Bead 600Ohms 1A")
      (fields
        (field (name "PART NUMBER") "MPZ1608S601ATA00")
        (field (name "MANUFACTURER") "TDK")
        (field (name "VALUE1") "1A")
      )
      (libsource (lib "HFPB_01-SchLib") (part "MPZ1608S601ATA00"))
    )
    (comp (ref "FB17")
      (value "600Ohms")
      (footprint "BEADC160X80X80L30N")
      (description "Ferrite Bead 600Ohms 1A")
      (fields
        (field (name "PART NUMBER") "MPZ1608S601ATA00")
        (field (name "MANUFACTURER") "TDK")
        (field (name "VALUE1") "1A")
      )
      (libsource (lib "HFPB_01-SchLib") (part "MPZ1608S601ATA00"))
    )
    (comp (ref "L1")
      (value "DLW5BTM142TQ2L")
      (footprint "MURATA_DLW5BTM142TQ2L")
      (description "Common Mode Choke 2 lines 1.4kOhm 2A 56mOhm")
      (fields (field (name "MANUFACTURER") "Murata") (field (name "ALTIUM_VALUE") "1.4kOhm"))
      (libsource (lib "") (part "DLW5BTM142TQ2L_1"))
    )
    (comp (ref "L2")
      (value "DLW5BTM142TQ2L")
      (footprint "MURATA_DLW5BTM142TQ2L")
      (description "Common Mode Choke 2 lines 1.4kOhm 2A 56mOhm")
      (fields (field (name "MANUFACTURER") "Murata") (field (name "ALTIUM_VALUE") "1.4kOhm"))
      (libsource (lib "HFPB_01-SchLib") (part "DLW5BTM142TQ2L"))
    )
    (comp (ref "L3")
      (value "DLW5BTM142TQ2L")
      (footprint "MURATA_DLW5BTM142TQ2L")
      (description "Common Mode Choke 2 lines 1.4kOhm 2A 56mOhm")
      (fields (field (name "MANUFACTURER") "Murata") (field (name "ALTIUM_VALUE") "1.4kOhm"))
      (libsource (lib "HFPB_01-SchLib") (part "DLW5BTM142TQ2L"))
    )
    (comp (ref "L4")
      (value "DLW5BTM142TQ2L")
      (footprint "MURATA_DLW5BTM142TQ2L")
      (description "Common Mode Choke 2 lines 1.4kOhm 2A 56mOhm")
      (fields (field (name "MANUFACTURER") "Murata") (field (name "ALTIUM_VALUE") "1.4kOhm"))
      (libsource (lib "") (part "DLW5BTM142TQ2L_1"))
    )
    (comp (ref "Q6")
      (value "IXTH240N15X4")
      (footprint "TO247-3 - sgib")
      (description "MOSFET N-chanel, 150V, 240A, 4.4mOhm")
      (fields (field (name "MANUFACTURER") "IXYS"))
      (libsource (lib "HFPB_01-SchLib") (part "IXTH240N15X4"))
    )
    (comp (ref "Q7")
      (value "IXTH240N15X4")
      (footprint "TO247-3 - short pins")
      (description "MOSFET N-chanel, 150V, 240A, 4.4mOhm")
      (fields (field (name "MANUFACTURER") "IXYS"))
      (libsource (lib "HFPB_01-SchLib") (part "IXTH240N15X4"))
    )
    (comp (ref "Q8")
      (value "IXTH240N15X4")
      (footprint "TO247-3 - short pins")
      (description "MOSFET N-chanel, 150V, 240A, 4.4mOhm")
      (fields (field (name "MANUFACTURER") "IXYS"))
      (libsource (lib "HFPB_01-SchLib") (part "IXTH240N15X4"))
    )
    (comp (ref "Q9")
      (value "IXTH240N15X4")
      (footprint "TO247-3 - sgib")
      (description "MOSFET N-chanel, 150V, 240A, 4.4mOhm")
      (fields (field (name "MANUFACTURER") "IXYS"))
      (libsource (lib "HFPB_01-SchLib") (part "IXTH240N15X4"))
    )
    (comp (ref "Q10")
      (value "IXTH240N15X4")
      (footprint "TO247-3 - sgib")
      (description "MOSFET N-chanel, 150V, 240A, 4.4mOhm")
      (fields (field (name "MANUFACTURER") "IXYS"))
      (libsource (lib "HFPB_01-SchLib") (part "IXTH240N15X4"))
    )
    (comp (ref "Q11")
      (value "IXTH240N15X4")
      (footprint "TO247-3 - short pins")
      (description "MOSFET N-chanel, 150V, 240A, 4.4mOhm")
      (fields (field (name "MANUFACTURER") "IXYS"))
      (libsource (lib "HFPB_01-SchLib") (part "IXTH240N15X4"))
    )
    (comp (ref "Q12")
      (value "IXTH240N15X4")
      (footprint "TO247-3 - short pins")
      (description "MOSFET N-chanel, 150V, 240A, 4.4mOhm")
      (fields (field (name "MANUFACTURER") "IXYS"))
      (libsource (lib "HFPB_01-SchLib") (part "IXTH240N15X4"))
    )
    (comp (ref "Q13")
      (value "IXTH240N15X4")
      (footprint "TO247-3 - sgib")
      (description "MOSFET N-chanel, 150V, 240A, 4.4mOhm")
      (fields (field (name "MANUFACTURER") "IXYS"))
      (libsource (lib "HFPB_01-SchLib") (part "IXTH240N15X4"))
    )
    (comp (ref "R85")
      (value "10k")
      (footprint "RESC160X80X55L30N - Full legend")
      (description "Resistor 0603")
      (fields (field (name "PART NUMBER") "ERJ-3EKF1002V") (field (name "MANUFACTURER") "Panasonic"))
      (libsource (lib "HFPB_01-SchLib") (part "R0603"))
    )
    (comp (ref "R86")
      (value "10k")
      (footprint "RESC160X80X55L30N - Full legend")
      (description "Resistor 0603")
      (fields (field (name "PART NUMBER") "ERJ-3EKF1002V") (field (name "MANUFACTURER") "Panasonic"))
      (libsource (lib "HFPB_01-SchLib") (part "R0603"))
    )
    (comp (ref "R87")
      (value "5.1k")
      (footprint "RESC160X80X55L30N - Full legend")
      (description "Resistor 0603")
      (fields (field (name "PART NUMBER") "ERJ-3EKF5101V") (field (name "MANUFACTURER") "Panasonic"))
      (libsource (lib "HFPB_01-SchLib") (part "R0603"))
    )
    (comp (ref "R88")
      (value "5.1k")
      (footprint "RESC160X80X55L30N - Full legend")
      (description "Resistor 0603")
      (fields (field (name "PART NUMBER") "ERJ-3EKF5101V") (field (name "MANUFACTURER") "Panasonic"))
      (libsource (lib "HFPB_01-SchLib") (part "R0603"))
    )
    (comp (ref "R89")
      (value "1k")
      (footprint "RESC160X80X55L30N - Full legend")
      (description "Resistor 0603")
      (fields (field (name "PART NUMBER") "ERJ-3EKF1001V") (field (name "MANUFACTURER") "Panasonic"))
      (libsource (lib "HFPB_01-SchLib") (part "R0603"))
    )
    (comp (ref "R90")
      (value "1k")
      (footprint "RESC160X80X55L30N - Full legend")
      (description "Resistor 0603")
      (fields (field (name "PART NUMBER") "ERJ-3EKF1001V") (field (name "MANUFACTURER") "Panasonic"))
      (libsource (lib "HFPB_01-SchLib") (part "R0603"))
    )
    (comp (ref "R91")
      (value "1k")
      (footprint "RESC160X80X55L30N - Full legend")
      (description "Resistor 0603")
      (fields (field (name "PART NUMBER") "ERJ-3EKF1001V") (field (name "MANUFACTURER") "Panasonic"))
      (libsource (lib "HFPB_01-SchLib") (part "R0603"))
    )
    (comp (ref "R92")
      (value "1k")
      (footprint "RESC160X80X55L30N - Full legend")
      (description "Resistor 0603")
      (fields (field (name "PART NUMBER") "ERJ-3EKF1001V") (field (name "MANUFACTURER") "Panasonic"))
      (libsource (lib "") (part "R0603_1"))
    )
    (comp (ref "R93")
      (value "100")
      (footprint "RESC160X80X55L30N - Full legend")
      (description "Resistor 0603")
      (fields (field (name "PART NUMBER") "ERJ-3EKF1000V") (field (name "MANUFACTURER") "Panasonic"))
      (libsource (lib "HFPB_01-SchLib") (part "R0603"))
    )
    (comp (ref "R94")
      (value "100")
      (footprint "RESC160X80X55L30N - Full legend")
      (description "Resistor 0603")
      (fields (field (name "PART NUMBER") "ERJ-3EKF1000V") (field (name "MANUFACTURER") "Panasonic"))
      (libsource (lib "HFPB_01-SchLib") (part "R0603"))
    )
    (comp (ref "R95")
      (value "1")
      (footprint "RESC200X125X70L40N - full legend")
      (description "Resistor 0805")
      (fields (field (name "PART NUMBER") "ERJ-6RQF1R0V") (field (name "MANUFACTURER") "Panasonic"))
      (libsource (lib "HFPB_01-SchLib") (part "R0805"))
    )
    (comp (ref "R95A")
      (value "1")
      (footprint "RESC200X125X70L40N - full legend")
      (description "Resistor 0805")
      (fields (field (name "PART NUMBER") "ERJ-6RQF1R0V") (field (name "MANUFACTURER") "Panasonic"))
      (libsource (lib "HFPB_01-SchLib") (part "R0805"))
    )
    (comp (ref "R96")
      (value "1")
      (footprint "RESC200X125X70L40N - full legend")
      (description "Resistor 0805")
      (fields (field (name "PART NUMBER") "ERJ-6RQF1R0V") (field (name "MANUFACTURER") "Panasonic"))
      (libsource (lib "HFPB_01-SchLib") (part "R0805"))
    )
    (comp (ref "R96A")
      (value "1")
      (footprint "RESC200X125X70L40N - full legend")
      (description "Resistor 0805")
      (fields (field (name "PART NUMBER") "ERJ-6RQF1R0V") (field (name "MANUFACTURER") "Panasonic"))
      (libsource (lib "HFPB_01-SchLib") (part "R0805"))
    )
    (comp (ref "R97")
      (value "1")
      (footprint "RESC200X125X70L40N - full legend")
      (description "Resistor 0805")
      (fields (field (name "PART NUMBER") "ERJ-6RQF1R0V") (field (name "MANUFACTURER") "Panasonic"))
      (libsource (lib "HFPB_01-SchLib") (part "R0805"))
    )
    (comp (ref "R97A")
      (value "1")
      (footprint "RESC200X125X70L40N - full legend")
      (description "Resistor 0805")
      (fields (field (name "PART NUMBER") "ERJ-6RQF1R0V") (field (name "MANUFACTURER") "Panasonic"))
      (libsource (lib "HFPB_01-SchLib") (part "R0805"))
    )
    (comp (ref "R98")
      (value "1")
      (footprint "RESC200X125X70L40N - full legend")
      (description "Resistor 0805")
      (fields (field (name "PART NUMBER") "ERJ-6RQF1R0V") (field (name "MANUFACTURER") "Panasonic"))
      (libsource (lib "HFPB_01-SchLib") (part "R0805"))
    )
    (comp (ref "R98A")
      (value "1")
      (footprint "RESC200X125X70L40N - full legend")
      (description "Resistor 0805")
      (fields (field (name "PART NUMBER") "ERJ-6RQF1R0V") (field (name "MANUFACTURER") "Panasonic"))
      (libsource (lib "HFPB_01-SchLib") (part "R0805"))
    )
    (comp (ref "R99")
      (value "10k")
      (footprint "RESC160X80X55L30N - Full legend")
      (description "Resistor 0603")
      (fields (field (name "PART NUMBER") "ERJ-3EKF1002V") (field (name "MANUFACTURER") "Panasonic"))
      (libsource (lib "HFPB_01-SchLib") (part "R0603"))
    )
    (comp (ref "R100")
      (value "51")
      (footprint "RESC640X320X70L60N")
      (description "Resistor 2512")
      (fields (field (name "PART NUMBER") "ERJ-1TYJ510U") (field (name "MANUFACTURER") "Panasonic"))
      (libsource (lib "HFPB_01-SchLib") (part "R2512"))
    )
    (comp (ref "R100A")
      (value "51")
      (footprint "RESC640X320X70L60N")
      (description "Resistor 2512")
      (fields (field (name "PART NUMBER") "ERJ-1TYJ510U") (field (name "MANUFACTURER") "Panasonic"))
      (libsource (lib "HFPB_01-SchLib") (part "R2512"))
    )
    (comp (ref "R100B")
      (value "51")
      (footprint "RESC640X320X70L60N")
      (description "Resistor 2512")
      (fields (field (name "PART NUMBER") "ERJ-1TYJ510U") (field (name "MANUFACTURER") "Panasonic"))
      (libsource (lib "HFPB_01-SchLib") (part "R2512"))
    )
    (comp (ref "R100C")
      (value "51")
      (footprint "RESC640X320X70L60N")
      (description "Resistor 2512")
      (fields (field (name "PART NUMBER") "ERJ-1TYJ510U") (field (name "MANUFACTURER") "Panasonic"))
      (libsource (lib "HFPB_01-SchLib") (part "R2512"))
    )
    (comp (ref "R101")
      (value "51")
      (footprint "RESC640X320X70L60N")
      (description "Resistor 2512")
      (fields (field (name "PART NUMBER") "ERJ-1TYJ510U") (field (name "MANUFACTURER") "Panasonic"))
      (libsource (lib "HFPB_01-SchLib") (part "R2512"))
    )
    (comp (ref "R101A")
      (value "51")
      (footprint "RESC640X320X70L60N")
      (description "Resistor 2512")
      (fields (field (name "PART NUMBER") "ERJ-1TYJ510U") (field (name "MANUFACTURER") "Panasonic"))
      (libsource (lib "HFPB_01-SchLib") (part "R2512"))
    )
    (comp (ref "R101B")
      (value "51")
      (footprint "RESC640X320X70L60N")
      (description "Resistor 2512")
      (fields (field (name "PART NUMBER") "ERJ-1TYJ510U") (field (name "MANUFACTURER") "Panasonic"))
      (libsource (lib "HFPB_01-SchLib") (part "R2512"))
    )
    (comp (ref "R101C")
      (value "51")
      (footprint "RESC640X320X70L60N")
      (description "Resistor 2512")
      (fields (field (name "PART NUMBER") "ERJ-1TYJ510U") (field (name "MANUFACTURER") "Panasonic"))
      (libsource (lib "HFPB_01-SchLib") (part "R2512"))
    )
    (comp (ref "R102")
      (value "10k")
      (footprint "RESC160X80X55L30N - Full legend")
      (description "Resistor 0603")
      (fields (field (name "PART NUMBER") "ERJ-3EKF1002V") (field (name "MANUFACTURER") "Panasonic"))
      (libsource (lib "HFPB_01-SchLib") (part "R0603"))
    )
    (comp (ref "R103")
      (value "1k")
      (footprint "RESC160X80X55L30N - Full legend")
      (description "Resistor 0603")
      (fields (field (name "PART NUMBER") "ERJ-3EKF1001V") (field (name "MANUFACTURER") "Panasonic"))
      (libsource (lib "HFPB_01-SchLib") (part "R0603"))
    )
    (comp (ref "R104")
      (value "1k")
      (footprint "RESC160X80X55L30N - Full legend")
      (description "Resistor 0603")
      (fields (field (name "PART NUMBER") "ERJ-3EKF1001V") (field (name "MANUFACTURER") "Panasonic"))
      (libsource (lib "HFPB_01-SchLib") (part "R0603"))
    )
    (comp (ref "R105")
      (value "1k")
      (footprint "RESC160X80X55L30N - Full legend")
      (description "Resistor 0603")
      (fields (field (name "PART NUMBER") "ERJ-3EKF1001V") (field (name "MANUFACTURER") "Panasonic"))
      (libsource (lib "HFPB_01-SchLib") (part "R0603"))
    )
    (comp (ref "R106")
      (value "1k")
      (footprint "RESC160X80X55L30N - Full legend")
      (description "Resistor 0603")
      (fields (field (name "PART NUMBER") "ERJ-3EKF1001V") (field (name "MANUFACTURER") "Panasonic"))
      (libsource (lib "") (part "R0603_1"))
    )
    (comp (ref "R107")
      (value "100")
      (footprint "RESC160X80X55L30N - Full legend")
      (description "Resistor 0603")
      (fields (field (name "PART NUMBER") "ERJ-3EKF1000V") (field (name "MANUFACTURER") "Panasonic"))
      (libsource (lib "HFPB_01-SchLib") (part "R0603"))
    )
    (comp (ref "R108")
      (value "100")
      (footprint "RESC160X80X55L30N - Full legend")
      (description "Resistor 0603")
      (fields (field (name "PART NUMBER") "ERJ-3EKF1000V") (field (name "MANUFACTURER") "Panasonic"))
      (libsource (lib "HFPB_01-SchLib") (part "R0603"))
    )
    (comp (ref "R109")
      (value "1")
      (footprint "RESC200X125X70L40N - full legend")
      (description "Resistor 0805")
      (fields (field (name "PART NUMBER") "ERJ-6RQF1R0V") (field (name "MANUFACTURER") "Panasonic"))
      (libsource (lib "HFPB_01-SchLib") (part "R0805"))
    )
    (comp (ref "R109A")
      (value "1")
      (footprint "RESC200X125X70L40N - full legend")
      (description "Resistor 0805")
      (fields (field (name "PART NUMBER") "ERJ-6RQF1R0V") (field (name "MANUFACTURER") "Panasonic"))
      (libsource (lib "HFPB_01-SchLib") (part "R0805"))
    )
    (comp (ref "R110")
      (value "1")
      (footprint "RESC200X125X70L40N - full legend")
      (description "Resistor 0805")
      (fields (field (name "PART NUMBER") "ERJ-6RQF1R0V") (field (name "MANUFACTURER") "Panasonic"))
      (libsource (lib "HFPB_01-SchLib") (part "R0805"))
    )
    (comp (ref "R110A")
      (value "1")
      (footprint "RESC200X125X70L40N - full legend")
      (description "Resistor 0805")
      (fields (field (name "PART NUMBER") "ERJ-6RQF1R0V") (field (name "MANUFACTURER") "Panasonic"))
      (libsource (lib "HFPB_01-SchLib") (part "R0805"))
    )
    (comp (ref "R111")
      (value "1")
      (footprint "RESC200X125X70L40N - full legend")
      (description "Resistor 0805")
      (fields (field (name "PART NUMBER") "ERJ-6RQF1R0V") (field (name "MANUFACTURER") "Panasonic"))
      (libsource (lib "HFPB_01-SchLib") (part "R0805"))
    )
    (comp (ref "R111A")
      (value "1")
      (footprint "RESC200X125X70L40N - full legend")
      (description "Resistor 0805")
      (fields (field (name "PART NUMBER") "ERJ-6RQF1R0V") (field (name "MANUFACTURER") "Panasonic"))
      (libsource (lib "HFPB_01-SchLib") (part "R0805"))
    )
    (comp (ref "R112")
      (value "1")
      (footprint "RESC200X125X70L40N - full legend")
      (description "Resistor 0805")
      (fields (field (name "PART NUMBER") "ERJ-6RQF1R0V") (field (name "MANUFACTURER") "Panasonic"))
      (libsource (lib "HFPB_01-SchLib") (part "R0805"))
    )
    (comp (ref "R112A")
      (value "1")
      (footprint "RESC200X125X70L40N - full legend")
      (description "Resistor 0805")
      (fields (field (name "PART NUMBER") "ERJ-6RQF1R0V") (field (name "MANUFACTURER") "Panasonic"))
      (libsource (lib "HFPB_01-SchLib") (part "R0805"))
    )
    (comp (ref "R113")
      (value "10k")
      (footprint "RESC160X80X55L30N - Full legend")
      (description "Resistor 0603")
      (fields (field (name "PART NUMBER") "ERJ-3EKF1002V") (field (name "MANUFACTURER") "Panasonic"))
      (libsource (lib "HFPB_01-SchLib") (part "R0603"))
    )
    (comp (ref "R114")
      (value "51")
      (footprint "RESC640X320X70L60N")
      (description "Resistor 2512")
      (fields (field (name "PART NUMBER") "ERJ-1TYJ510U") (field (name "MANUFACTURER") "Panasonic"))
      (libsource (lib "HFPB_01-SchLib") (part "R2512"))
    )
    (comp (ref "R114A")
      (value "51")
      (footprint "RESC640X320X70L60N")
      (description "Resistor 2512")
      (fields (field (name "PART NUMBER") "ERJ-1TYJ510U") (field (name "MANUFACTURER") "Panasonic"))
      (libsource (lib "HFPB_01-SchLib") (part "R2512"))
    )
    (comp (ref "R114B")
      (value "51")
      (footprint "RESC640X320X70L60N")
      (description "Resistor 2512")
      (fields (field (name "PART NUMBER") "ERJ-1TYJ510U") (field (name "MANUFACTURER") "Panasonic"))
      (libsource (lib "HFPB_01-SchLib") (part "R2512"))
    )
    (comp (ref "R114C")
      (value "51")
      (footprint "RESC640X320X70L60N")
      (description "Resistor 2512")
      (fields (field (name "PART NUMBER") "ERJ-1TYJ510U") (field (name "MANUFACTURER") "Panasonic"))
      (libsource (lib "HFPB_01-SchLib") (part "R2512"))
    )
    (comp (ref "R115")
      (value "51")
      (footprint "RESC640X320X70L60N")
      (description "Resistor 2512")
      (fields (field (name "PART NUMBER") "ERJ-1TYJ510U") (field (name "MANUFACTURER") "Panasonic"))
      (libsource (lib "HFPB_01-SchLib") (part "R2512"))
    )
    (comp (ref "R115A")
      (value "51")
      (footprint "RESC640X320X70L60N")
      (description "Resistor 2512")
      (fields (field (name "PART NUMBER") "ERJ-1TYJ510U") (field (name "MANUFACTURER") "Panasonic"))
      (libsource (lib "HFPB_01-SchLib") (part "R2512"))
    )
    (comp (ref "R115B")
      (value "51")
      (footprint "RESC640X320X70L60N")
      (description "Resistor 2512")
      (fields (field (name "PART NUMBER") "ERJ-1TYJ510U") (field (name "MANUFACTURER") "Panasonic"))
      (libsource (lib "HFPB_01-SchLib") (part "R2512"))
    )
    (comp (ref "R115C")
      (value "51")
      (footprint "RESC640X320X70L60N")
      (description "Resistor 2512")
      (fields (field (name "PART NUMBER") "ERJ-1TYJ510U") (field (name "MANUFACTURER") "Panasonic"))
      (libsource (lib "HFPB_01-SchLib") (part "R2512"))
    )
    (comp (ref "R116")
      (value "10k")
      (footprint "RESC160X80X55L30N - Full legend")
      (description "Resistor 0603")
      (fields (field (name "PART NUMBER") "ERJ-3EKF1002V") (field (name "MANUFACTURER") "Panasonic"))
      (libsource (lib "HFPB_01-SchLib") (part "R0603"))
    )
    (comp (ref "R117")
      (value "100")
      (footprint "RESC160X80X55L30N - Full legend")
      (description "Resistor 0603")
      (fields (field (name "PART NUMBER") "ERJ-3EKF1000V") (field (name "MANUFACTURER") "Panasonic"))
      (libsource (lib "") (part "R0603_2"))
    )
    (comp (ref "R118")
      (value "5mOhms")
      (footprint "RESC670X720X125L115N")
      (description "Resistor 2728")
      (fields
        (field (name "PART NUMBER") "CSSH2728FT5L00")
        (field (name "MANUFACTURER") "Stackpole")
        (field (name "VALUE1") "1%")
      )
      (libsource (lib "HFPB_01-SchLib") (part "R2728"))
    )
    (comp (ref "R119")
      (value "10k")
      (footprint "RESC160X80X55L30N - Full legend")
      (description "Resistor 0603")
      (fields (field (name "PART NUMBER") "ERJ-3EKF1002V") (field (name "MANUFACTURER") "Panasonic"))
      (libsource (lib "HFPB_01-SchLib") (part "R0603"))
    )
    (comp (ref "R120")
      (value "10k")
      (footprint "RESC160X80X55L30N - Full legend")
      (description "Resistor 0603")
      (fields (field (name "PART NUMBER") "ERJ-3EKF1002V") (field (name "MANUFACTURER") "Panasonic"))
      (libsource (lib "HFPB_01-SchLib") (part "R0603"))
    )
    (comp (ref "R121")
      (value "0")
      (footprint "RESC200X125X70L40N - full legend")
      (description "Resistor 0805")
      (fields (field (name "PART NUMBER") "ERJ-6GEY0R00V") (field (name "MANUFACTURER") "Panasonic"))
      (libsource (lib "HFPB_01-SchLib") (part "R0805"))
    )
    (comp (ref "R122")
      (value "5.1k")
      (footprint "RESC160X80X55L30N - Full legend")
      (description "Resistor 0603")
      (fields (field (name "PART NUMBER") "ERJ-3EKF5101V") (field (name "MANUFACTURER") "Panasonic"))
      (libsource (lib "HFPB_01-SchLib") (part "R0603"))
    )
    (comp (ref "R123")
      (value "5.1k")
      (footprint "RESC160X80X55L30N - Full legend")
      (description "Resistor 0603")
      (fields (field (name "PART NUMBER") "ERJ-3EKF5101V") (field (name "MANUFACTURER") "Panasonic"))
      (libsource (lib "HFPB_01-SchLib") (part "R0603"))
    )
    (comp (ref "TP7")
      (value "NC")
      (footprint "hole/0.8/1.4-R")
      (description "Test point")
      (libsource (lib "HFPB_01-SchLib") (part "TEST POINT"))
    )
    (comp (ref "TP8")
      (value "NC")
      (footprint "hole/0.8/1.4-R")
      (description "Test point")
      (libsource (lib "HFPB_01-SchLib") (part "TEST POINT"))
    )
    (comp (ref "TP9")
      (value "NC")
      (footprint "hole/0.8/1.4-R")
      (description "Test point")
      (libsource (lib "HFPB_01-SchLib") (part "TEST POINT"))
    )
    (comp (ref "TP10")
      (value "NC")
      (footprint "hole/0.8/1.4-R")
      (description "Test point")
      (libsource (lib "HFPB_01-SchLib") (part "TEST POINT"))
    )
    (comp (ref "TP11")
      (value "NC")
      (footprint "hole/0.8/1.4-R")
      (description "Test point")
      (libsource (lib "HFPB_01-SchLib") (part "TEST POINT"))
    )
    (comp (ref "TP12")
      (value "NC")
      (footprint "hole/0.8/1.4-R")
      (description "Test point")
      (libsource (lib "HFPB_01-SchLib") (part "TEST POINT"))
    )
    (comp (ref "TP13")
      (value "NC")
      (footprint "hole/0.8/1.4-R")
      (description "Test point")
      (libsource (lib "HFPB_01-SchLib") (part "TEST POINT"))
    )
    (comp (ref "TP14")
      (value "NC")
      (footprint "hole/0.8/1.4-R")
      (description "Test point")
      (libsource (lib "HFPB_01-SchLib") (part "TEST POINT"))
    )
    (comp (ref "U8")
      (value "EC4SAW-24S15N")
      (footprint "SIP950W50P254L2200H1150Q8")
      (description "DC/DC Converter 6W 1.5kV Isolated")
      (fields (field (name "MANUFACTURER") "Cincon") (field (name "PACKAGE/CASE") "SIP-8"))
      (libsource (lib "HFPB_01-SchLib") (part "EC4SAW-24S15N"))
    )
    (comp (ref "U9")
      (value "TPS71550DCKR")
      (footprint "SOT23-5P65_210X110L36X22N")
      (description "LDO 5.0V 50mA")
      (fields (field (name "MANUFACTURER") "Texas Instruments") (field (name "PACKAGE/CASE") "SC70-5"))
      (libsource (lib "") (part "TPS71550DCKR_1"))
    )
    (comp (ref "U10")
      (value "TPS71550DCKR")
      (footprint "SOT23-5P65_210X110L36X22N")
      (description "LDO 5.0V 50mA")
      (fields (field (name "MANUFACTURER") "Texas Instruments") (field (name "PACKAGE/CASE") "SC70-5"))
      (libsource (lib "HFPB_01-SchLib") (part "TPS71550DCKR"))
    )
    (comp (ref "U11")
      (value "EC4SAW-24S15N")
      (footprint "SIP950W50P254L2200H1150Q8")
      (description "DC/DC Converter 6W 1.5kV Isolated")
      (fields (field (name "MANUFACTURER") "Cincon") (field (name "PACKAGE/CASE") "SIP-8"))
      (libsource (lib "") (part "EC4SAW-24S15N_1"))
    )
    (comp (ref "U12")
      (value "SI8620BC-B-ISR")
      (footprint "SOIC-8")
      (description "Digital Isolator 3750Vrms 2 Channel 150Mbps")
      (fields (field (name "MANUFACTURER") "Silicon Labs") (field (name "PACKAGE/CASE") "SOIC-8"))
      (libsource (lib "HFPB_01-SchLib") (part "SI8620BC-B-ISR"))
    )
    (comp (ref "U13")
      (value "SI8620BC-B-ISR")
      (footprint "SOIC-8")
      (description "Digital Isolator 3750Vrms 2 Channel 150Mbps")
      (fields (field (name "MANUFACTURER") "Silicon Labs") (field (name "PACKAGE/CASE") "SOIC-8"))
      (libsource (lib "") (part "SI8620BC-B-ISR_1"))
    )
    (comp (ref "U14")
      (value "IXDD614YI")
      (footprint "DPAK6P170_1524X482L228X75T770X800N")
      (description "MOSFET Driver IC")
      (fields (field (name "MANUFACTURER") "IXYS") (field (name "PACKAGE/CASE") "TO263-5"))
      (libsource (lib "") (part "IXDD614YI_1"))
    )
    (comp (ref "U15")
      (value "IXDD614YI")
      (footprint "DPAK6P170_1524X482L228X75T770X800N")
      (description "MOSFET Driver IC")
      (fields (field (name "MANUFACTURER") "IXYS") (field (name "PACKAGE/CASE") "TO263-5"))
      (libsource (lib "HFPB_01-SchLib") (part "IXDD614YI"))
    )
    (comp (ref "U16")
      (value "SI8620BC-B-ISR")
      (footprint "SOIC-8")
      (description "Digital Isolator 3750Vrms 2 Channel 150Mbps")
      (fields (field (name "MANUFACTURER") "Silicon Labs") (field (name "PACKAGE/CASE") "SOIC-8"))
      (libsource (lib "HFPB_01-SchLib") (part "SI8620BC-B-ISR"))
    )
    (comp (ref "U17")
      (value "SI8620BC-B-ISR")
      (footprint "SOIC-8")
      (description "Digital Isolator 3750Vrms 2 Channel 150Mbps")
      (fields (field (name "MANUFACTURER") "Silicon Labs") (field (name "PACKAGE/CASE") "SOIC-8"))
      (libsource (lib "") (part "SI8620BC-B-ISR_1"))
    )
    (comp (ref "U18")
      (value "IXDD614YI")
      (footprint "DPAK6P170_1524X482L228X75T770X800N")
      (description "MOSFET Driver IC")
      (fields (field (name "MANUFACTURER") "IXYS") (field (name "PACKAGE/CASE") "TO263-5"))
      (libsource (lib "") (part "IXDD614YI_1"))
    )
    (comp (ref "U19")
      (value "IXDD614YI")
      (footprint "DPAK6P170_1524X482L228X75T770X800N")
      (description "MOSFET Driver IC")
      (fields (field (name "MANUFACTURER") "IXYS") (field (name "PACKAGE/CASE") "TO263-5"))
      (libsource (lib "HFPB_01-SchLib") (part "IXDD614YI"))
    )
    (comp (ref "U20")
      (value "EC4SAW-24S15N")
      (footprint "SIP950W50P254L2200H1150Q8")
      (description "DC/DC Converter 6W 1.5kV Isolated")
      (fields (field (name "MANUFACTURER") "Cincon") (field (name "PACKAGE/CASE") "SIP-8"))
      (libsource (lib "HFPB_01-SchLib") (part "EC4SAW-24S15N"))
    )
    (comp (ref "U21")
      (value "EC4SAW-24S15N")
      (footprint "SIP950W50P254L2200H1150Q8")
      (description "DC/DC Converter 6W 1.5kV Isolated")
      (fields (field (name "MANUFACTURER") "Cincon") (field (name "PACKAGE/CASE") "SIP-8"))
      (libsource (lib "") (part "EC4SAW-24S15N_1"))
    )
    (comp (ref "U22")
      (value "TPS71550DCKR")
      (footprint "SOT23-5P65_210X110L36X22N")
      (description "LDO 5.0V 50mA")
      (fields (field (name "MANUFACTURER") "Texas Instruments") (field (name "PACKAGE/CASE") "SC70-5"))
      (libsource (lib "") (part "TPS71550DCKR_1"))
    )
    (comp (ref "U23")
      (value "TPS71550DCKR")
      (footprint "SOT23-5P65_210X110L36X22N")
      (description "LDO 5.0V 50mA")
      (fields (field (name "MANUFACTURER") "Texas Instruments") (field (name "PACKAGE/CASE") "SC70-5"))
      (libsource (lib "HFPB_01-SchLib") (part "TPS71550DCKR"))
    )
    (comp (ref "X10")
      (value "7461097")
      (footprint "Wurth_7461097")
      (description "Screw Terminal M6 16 pin")
      (fields (field (name "MANUFACTURER") "Wurth Elektronik") (field (name "MATING WITH") "M6 connector"))
      (libsource (lib "") (part "7461097_2"))
    )
    (comp (ref "X11")
      (value "7461097")
      (footprint "Wurth_7461097")
      (description "Screw Terminal M6 16 pin")
      (fields (field (name "MANUFACTURER") "Wurth Elektronik") (field (name "MATING WITH") "M6 connector"))
      (libsource (lib "") (part "7461097_3"))
    )
    (comp (ref "X12")
      (value "7461097")
      (footprint "Wurth_7461097")
      (description "Screw Terminal M6 16 pin")
      (fields (field (name "MANUFACTURER") "Wurth Elektronik") (field (name "MATING WITH") "M6 connector"))
      (libsource (lib "HFPB_01-SchLib") (part "7461097"))
    )
    (comp (ref "X13")
      (value "7461097")
      (footprint "Wurth_7461097")
      (description "Screw Terminal M6 16 pin")
      (fields (field (name "MANUFACTURER") "Wurth Elektronik") (field (name "MATING WITH") "M6 connector"))
      (libsource (lib "") (part "7461097_1"))
    )
  )
  (nets
    (net (code "1") (name "+(15-30)V") (class "Default")
      (node (ref "C131") (pin "1") (pinfunction "1_1") (pintype "passive"))
      (node (ref "C134") (pin "1") (pinfunction "1_1") (pintype "passive"))
      (node (ref "C88") (pin "1") (pinfunction "1_1") (pintype "passive"))
      (node (ref "C91") (pin "1") (pinfunction "1_1") (pintype "passive"))
      (node (ref "FB14") (pin "1") (pinfunction "1_1") (pintype "passive"))
      (node (ref "FB15") (pin "1") (pinfunction "1_1") (pintype "passive"))
      (node (ref "FB6") (pin "1") (pinfunction "1_1") (pintype "passive"))
      (node (ref "FB9") (pin "1") (pinfunction "1_1") (pintype "passive"))
    )
    (net (code "2") (name "+3.3V'") (class "Default")
      (node (ref "FB10") (pin "1") (pinfunction "1_1") (pintype "passive"))
      (node (ref "FB11") (pin "1") (pinfunction "1_1") (pintype "passive"))
      (node (ref "FB12") (pin "1") (pinfunction "1_1") (pintype "passive"))
      (node (ref "FB13") (pin "1") (pinfunction "1_1") (pintype "passive"))
    )
    (net (code "3") (name "+5.0V_1") (class "Default")
      (node (ref "C92") (pin "1") (pinfunction "1_1") (pintype "passive"))
      (node (ref "U12") (pin "8") (pinfunction "Vdd2_8") (pintype "power_in"))
      (node (ref "U9") (pin "5") (pinfunction "OUT_5") (pintype "power_in"))
    )
    (net (code "4") (name "+5.0V_2") (class "Default")
      (node (ref "C108") (pin "1") (pinfunction "1_1") (pintype "passive"))
      (node (ref "U16") (pin "8") (pinfunction "Vdd2_8") (pintype "power_in"))
      (node (ref "U22") (pin "5") (pinfunction "OUT_5") (pintype "power_in"))
    )
    (net (code "5") (name "+5.0V_3") (class "Default")
      (node (ref "C93") (pin "1") (pinfunction "1_1") (pintype "passive"))
      (node (ref "U10") (pin "5") (pinfunction "OUT_5") (pintype "power_in"))
      (node (ref "U13") (pin "8") (pinfunction "Vdd2_8") (pintype "power_in"))
    )
    (net (code "6") (name "+5.0V_4") (class "Default")
      (node (ref "C109") (pin "1") (pinfunction "1_1") (pintype "passive"))
      (node (ref "U17") (pin "8") (pinfunction "Vdd2_8") (pintype "power_in"))
      (node (ref "U23") (pin "5") (pinfunction "OUT_5") (pintype "power_in"))
    )
    (net (code "7") (name "+5V_1") (class "Default")
      (node (ref "C100") (pin "2") (pinfunction "2_2") (pintype "passive"))
      (node (ref "C101") (pin "2") (pinfunction "2_2") (pintype "passive"))
      (node (ref "C104") (pin "1") (pinfunction "1_1") (pintype "passive"))
      (node (ref "C105") (pin "1") (pinfunction "1_1") (pintype "passive"))
      (node (ref "C112") (pin "1") (pinfunction "1_1") (pintype "passive"))
      (node (ref "C80") (pin "2") (pinfunction "2_2") (pintype "passive"))
      (node (ref "C89") (pin "1") (pinfunction "1_1") (pintype "passive"))
      (node (ref "Q10") (pin "2") (pinfunction "D_2") (pintype "passive"))
      (node (ref "Q11") (pin "2") (pinfunction "D_2") (pintype "passive"))
      (node (ref "Q6") (pin "3") (pinfunction "S_3") (pintype "passive"))
      (node (ref "Q7") (pin "3") (pinfunction "S_3") (pintype "passive"))
      (node (ref "R100") (pin "1") (pinfunction "1_1") (pintype "passive"))
      (node (ref "R100A") (pin "1") (pinfunction "1_1") (pintype "passive"))
      (node (ref "R100B") (pin "1") (pinfunction "1_1") (pintype "passive"))
      (node (ref "R100C") (pin "1") (pinfunction "1_1") (pintype "passive"))
      (node (ref "R85") (pin "1") (pinfunction "1_1") (pintype "passive"))
      (node (ref "R87") (pin "2") (pinfunction "2_2") (pintype "passive"))
      (node (ref "R99") (pin "1") (pinfunction "1_1") (pintype "passive"))
      (node (ref "X12") (pin "1") (pinfunction "1_1") (pintype "passive"))
    )
    (net (code "8") (name "+5V_2") (class "Default")
      (node (ref "C116") (pin "2") (pinfunction "2_2") (pintype "passive"))
      (node (ref "C117") (pin "2") (pinfunction "2_2") (pintype "passive"))
      (node (ref "C118") (pin "2") (pinfunction "2_2") (pintype "passive"))
      (node (ref "C119") (pin "2") (pinfunction "2_2") (pintype "passive"))
      (node (ref "C120") (pin "1") (pinfunction "1_1") (pintype "passive"))
      (node (ref "C121") (pin "1") (pinfunction "1_1") (pintype "passive"))
      (node (ref "C122") (pin "1") (pinfunction "1_1") (pintype "passive"))
      (node (ref "C123") (pin "1") (pinfunction "1_1") (pintype "passive"))
      (node (ref "C125") (pin "2") (pinfunction "2_2") (pintype "passive"))
      (node (ref "C126") (pin "2") (pinfunction "2_2") (pintype "passive"))
      (node (ref "C132") (pin "1") (pinfunction "1_1") (pintype "passive"))
      (node (ref "C133") (pin "1") (pinfunction "1_1") (pintype "passive"))
      (node (ref "C50") (pin "N") (pinfunction "N_N") (pintype "passive"))
      (node (ref "C51") (pin "N") (pinfunction "N_N") (pintype "passive"))
      (node (ref "C52") (pin "N") (pinfunction "N_N") (pintype "passive"))
      (node (ref "C53") (pin "N") (pinfunction "N_N") (pintype "passive"))
      (node (ref "C54") (pin "N") (pinfunction "N_N") (pintype "passive"))
      (node (ref "C55") (pin "N") (pinfunction "N_N") (pintype "passive"))
      (node (ref "C56") (pin "N") (pinfunction "N_N") (pintype "passive"))
      (node (ref "C57") (pin "N") (pinfunction "N_N") (pintype "passive"))
      (node (ref "C58") (pin "N") (pinfunction "N_N") (pintype "passive"))
      (node (ref "C59") (pin "N") (pinfunction "N_N") (pintype "passive"))
      (node (ref "C60") (pin "N") (pinfunction "N_N") (pintype "passive"))
      (node (ref "C61") (pin "N") (pinfunction "N_N") (pintype "passive"))
      (node (ref "C62") (pin "N") (pinfunction "N_N") (pintype "passive"))
      (node (ref "C63") (pin "N") (pinfunction "N_N") (pintype "passive"))
      (node (ref "C64") (pin "N") (pinfunction "N_N") (pintype "passive"))
      (node (ref "C65") (pin "N") (pinfunction "N_N") (pintype "passive"))
      (node (ref "C66") (pin "N") (pinfunction "N_N") (pintype "passive"))
      (node (ref "C67") (pin "N") (pinfunction "N_N") (pintype "passive"))
      (node (ref "C68") (pin "N") (pinfunction "N_N") (pintype "passive"))
      (node (ref "C69") (pin "N") (pinfunction "N_N") (pintype "passive"))
      (node (ref "C70") (pin "2") (pinfunction "2_2") (pintype "passive"))
      (node (ref "C71") (pin "2") (pinfunction "2_2") (pintype "passive"))
      (node (ref "C72") (pin "2") (pinfunction "2_2") (pintype "passive"))
      (node (ref "C73") (pin "2") (pinfunction "2_2") (pintype "passive"))
      (node (ref "C74") (pin "2") (pinfunction "2_2") (pintype "passive"))
      (node (ref "C75") (pin "2") (pinfunction "2_2") (pintype "passive"))
      (node (ref "C76") (pin "2") (pinfunction "2_2") (pintype "passive"))
      (node (ref "C77") (pin "2") (pinfunction "2_2") (pintype "passive"))
      (node (ref "C78") (pin "2") (pinfunction "2_2") (pintype "passive"))
      (node (ref "C79") (pin "2") (pinfunction "2_2") (pintype "passive"))
      (node (ref "Q10") (pin "3") (pinfunction "S_3") (pintype "passive"))
      (node (ref "Q11") (pin "3") (pinfunction "S_3") (pintype "passive"))
      (node (ref "Q12") (pin "3") (pinfunction "S_3") (pintype "passive"))
      (node (ref "Q13") (pin "3") (pinfunction "S_3") (pintype "passive"))
      (node (ref "R113") (pin "1") (pinfunction "1_1") (pintype "passive"))
      (node (ref "R114") (pin "1") (pinfunction "1_1") (pintype "passive"))
      (node (ref "R114A") (pin "1") (pinfunction "1_1") (pintype "passive"))
      (node (ref "R114B") (pin "1") (pinfunction "1_1") (pintype "passive"))
      (node (ref "R114C") (pin "1") (pinfunction "1_1") (pintype "passive"))
      (node (ref "R115") (pin "1") (pinfunction "1_1") (pintype "passive"))
      (node (ref "R115A") (pin "1") (pinfunction "1_1") (pintype "passive"))
      (node (ref "R115B") (pin "1") (pinfunction "1_1") (pintype "passive"))
      (node (ref "R115C") (pin "1") (pinfunction "1_1") (pintype "passive"))
      (node (ref "R116") (pin "1") (pinfunction "1_1") (pintype "passive"))
      (node (ref "R117") (pin "1") (pinfunction "1_1") (pintype "passive"))
      (node (ref "R118") (pin "2") (pinfunction "2_2") (pintype "passive"))
      (node (ref "R119") (pin "1") (pinfunction "1_1") (pintype "passive"))
      (node (ref "R120") (pin "1") (pinfunction "1_1") (pintype "passive"))
      (node (ref "R122") (pin "2") (pinfunction "2_2") (pintype "passive"))
      (node (ref "R123") (pin "2") (pinfunction "2_2") (pintype "passive"))
    )
    (net (code "9") (name "+5V_3") (class "Default")
      (node (ref "C102") (pin "2") (pinfunction "2_2") (pintype "passive"))
      (node (ref "C103") (pin "2") (pinfunction "2_2") (pintype "passive"))
      (node (ref "C106") (pin "1") (pinfunction "1_1") (pintype "passive"))
      (node (ref "C107") (pin "1") (pinfunction "1_1") (pintype "passive"))
      (node (ref "C113") (pin "1") (pinfunction "1_1") (pintype "passive"))
      (node (ref "C81") (pin "2") (pinfunction "2_2") (pintype "passive"))
      (node (ref "C90") (pin "1") (pinfunction "1_1") (pintype "passive"))
      (node (ref "Q12") (pin "2") (pinfunction "D_2") (pintype "passive"))
      (node (ref "Q13") (pin "2") (pinfunction "D_2") (pintype "passive"))
      (node (ref "Q8") (pin "3") (pinfunction "S_3") (pintype "passive"))
      (node (ref "Q9") (pin "3") (pinfunction "S_3") (pintype "passive"))
      (node (ref "R101") (pin "1") (pinfunction "1_1") (pintype "passive"))
      (node (ref "R101A") (pin "1") (pinfunction "1_1") (pintype "passive"))
      (node (ref "R101B") (pin "1") (pinfunction "1_1") (pintype "passive"))
      (node (ref "R101C") (pin "1") (pinfunction "1_1") (pintype "passive"))
      (node (ref "R102") (pin "1") (pinfunction "1_1") (pintype "passive"))
      (node (ref "R86") (pin "1") (pinfunction "1_1") (pintype "passive"))
      (node (ref "R88") (pin "2") (pinfunction "2_2") (pintype "passive"))
      (node (ref "X13") (pin "1") (pinfunction "1_1") (pintype "passive"))
    )
    (net (code "10") (name "+15V_1") (class "Default")
      (node (ref "C100") (pin "1") (pinfunction "1_1") (pintype "passive"))
      (node (ref "C101") (pin "1") (pinfunction "1_1") (pintype "passive"))
      (node (ref "C80") (pin "1") (pinfunction "1_1") (pintype "passive"))
      (node (ref "D10") (pin "C") (pinfunction "C_C") (pintype "passive"))
      (node (ref "FB7") (pin "1") (pinfunction "1_1") (pintype "passive"))
      (node (ref "L1") (pin "3") (pinfunction "3_3") (pintype "passive"))
      (node (ref "R85") (pin "2") (pinfunction "2_2") (pintype "passive"))
      (node (ref "R89") (pin "2") (pinfunction "2_2") (pintype "passive"))
      (node (ref "U14") (pin "1") (pinfunction "VCC_1") (pintype "power_in"))
    )
    (net (code "11") (name "+15V_2") (class "Default")
      (node (ref "C116") (pin "1") (pinfunction "1_1") (pintype "passive"))
      (node (ref "C117") (pin "1") (pinfunction "1_1") (pintype "passive"))
      (node (ref "C125") (pin "1") (pinfunction "1_1") (pintype "passive"))
      (node (ref "D14") (pin "C") (pinfunction "C_C") (pintype "passive"))
      (node (ref "FB16") (pin "1") (pinfunction "1_1") (pintype "passive"))
      (node (ref "L3") (pin "2") (pinfunction "2_2") (pintype "passive"))
      (node (ref "R103") (pin "2") (pinfunction "2_2") (pintype "passive"))
      (node (ref "R119") (pin "2") (pinfunction "2_2") (pintype "passive"))
      (node (ref "U18") (pin "1") (pinfunction "VCC_1") (pintype "power_in"))
    )
    (net (code "12") (name "+15V_3") (class "Default")
      (node (ref "C102") (pin "1") (pinfunction "1_1") (pintype "passive"))
      (node (ref "C103") (pin "1") (pinfunction "1_1") (pintype "passive"))
      (node (ref "C81") (pin "1") (pinfunction "1_1") (pintype "passive"))
      (node (ref "D11") (pin "C") (pinfunction "C_C") (pintype "passive"))
      (node (ref "FB8") (pin "1") (pinfunction "1_1") (pintype "passive"))
      (node (ref "L2") (pin "3") (pinfunction "3_3") (pintype "passive"))
      (node (ref "R86") (pin "2") (pinfunction "2_2") (pintype "passive"))
      (node (ref "R90") (pin "1") (pinfunction "1_1") (pintype "passive"))
      (node (ref "U15") (pin "1") (pinfunction "VCC_1") (pintype "power_in"))
    )
    (net (code "13") (name "+15V_4") (class "Default")
      (node (ref "C118") (pin "1") (pinfunction "1_1") (pintype "passive"))
      (node (ref "C119") (pin "1") (pinfunction "1_1") (pintype "passive"))
      (node (ref "C126") (pin "1") (pinfunction "1_1") (pintype "passive"))
      (node (ref "D15") (pin "C") (pinfunction "C_C") (pintype "passive"))
      (node (ref "FB17") (pin "1") (pinfunction "1_1") (pintype "passive"))
      (node (ref "L4") (pin "2") (pinfunction "2_2") (pintype "passive"))
      (node (ref "R104") (pin "1") (pinfunction "1_1") (pintype "passive"))
      (node (ref "R120") (pin "2") (pinfunction "2_2") (pintype "passive"))
      (node (ref "U19") (pin "1") (pinfunction "VCC_1") (pintype "power_in"))
    )
    (net (code "14") (name "+HV") (class "Default")
      (node (ref "C50") (pin "P") (pinfunction "P_P") (pintype "passive"))
      (node (ref "C51") (pin "P") (pinfunction "P_P") (pintype "passive"))
      (node (ref "C52") (pin "P") (pinfunction "P_P") (pintype "passive"))
      (node (ref "C53") (pin "P") (pinfunction "P_P") (pintype "passive"))
      (node (ref "C54") (pin "P") (pinfunction "P_P") (pintype "passive"))
      (node (ref "C55") (pin "P") (pinfunction "P_P") (pintype "passive"))
      (node (ref "C56") (pin "P") (pinfunction "P_P") (pintype "passive"))
      (node (ref "C57") (pin "P") (pinfunction "P_P") (pintype "passive"))
      (node (ref "C58") (pin "P") (pinfunction "P_P") (pintype "passive"))
      (node (ref "C59") (pin "P") (pinfunction "P_P") (pintype "passive"))
      (node (ref "C60") (pin "P") (pinfunction "P_P") (pintype "passive"))
      (node (ref "C61") (pin "P") (pinfunction "P_P") (pintype "passive"))
      (node (ref "C62") (pin "P") (pinfunction "P_P") (pintype "passive"))
      (node (ref "C63") (pin "P") (pinfunction "P_P") (pintype "passive"))
      (node (ref "C64") (pin "P") (pinfunction "P_P") (pintype "passive"))
      (node (ref "C65") (pin "P") (pinfunction "P_P") (pintype "passive"))
      (node (ref "C66") (pin "P") (pinfunction "P_P") (pintype "passive"))
      (node (ref "C67") (pin "P") (pinfunction "P_P") (pintype "passive"))
      (node (ref "C68") (pin "P") (pinfunction "P_P") (pintype "passive"))
      (node (ref "C69") (pin "P") (pinfunction "P_P") (pintype "passive"))
      (node (ref "C70") (pin "1") (pinfunction "1_1") (pintype "passive"))
      (node (ref "C71") (pin "1") (pinfunction "1_1") (pintype "passive"))
      (node (ref "C72") (pin "1") (pinfunction "1_1") (pintype "passive"))
      (node (ref "C73") (pin "1") (pinfunction "1_1") (pintype "passive"))
      (node (ref "C74") (pin "1") (pinfunction "1_1") (pintype "passive"))
      (node (ref "C75") (pin "1") (pinfunction "1_1") (pintype "passive"))
      (node (ref "C76") (pin "1") (pinfunction "1_1") (pintype "passive"))
      (node (ref "C77") (pin "1") (pinfunction "1_1") (pintype "passive"))
      (node (ref "C78") (pin "1") (pinfunction "1_1") (pintype "passive"))
      (node (ref "C79") (pin "1") (pinfunction "1_1") (pintype "passive"))
      (node (ref "C96") (pin "1") (pinfunction "1_1") (pintype "passive"))
      (node (ref "C97") (pin "1") (pinfunction "1_1") (pintype "passive"))
      (node (ref "Q6") (pin "2") (pinfunction "D_2") (pintype "passive"))
      (node (ref "Q7") (pin "2") (pinfunction "D_2") (pintype "passive"))
      (node (ref "Q8") (pin "2") (pinfunction "D_2") (pintype "passive"))
      (node (ref "Q9") (pin "2") (pinfunction "D_2") (pintype "passive"))
      (node (ref "X10") (pin "1") (pinfunction "1_1") (pintype "passive"))
    )
    (net (code "15") (name "Current_Sense") (class "Default")
      (node (ref "C124") (pin "1") (pinfunction "1_1") (pintype "passive"))
      (node (ref "R117") (pin "2") (pinfunction "2_2") (pintype "passive"))
    )
    (net (code "16") (name "ENABLE") (class "Default")
      (node (ref "R105") (pin "1") (pinfunction "1_1") (pintype "passive"))
      (node (ref "R106") (pin "1") (pinfunction "1_1") (pintype "passive"))
      (node (ref "R91") (pin "1") (pinfunction "1_1") (pintype "passive"))
      (node (ref "R92") (pin "1") (pinfunction "1_1") (pintype "passive"))
    )
    (net (code "17") (name "GND") (class "Default")
      (node (ref "C110") (pin "2") (pinfunction "2_2") (pintype "passive"))
      (node (ref "C111") (pin "2") (pinfunction "2_2") (pintype "passive"))
      (node (ref "C124") (pin "2") (pinfunction "2_2") (pintype "passive"))
      (node (ref "C127") (pin "2") (pinfunction "2_2") (pintype "passive"))
      (node (ref "C130") (pin "2") (pinfunction "2_2") (pintype "passive"))
      (node (ref "C131") (pin "2") (pinfunction "2_2") (pintype "passive"))
      (node (ref "C134") (pin "2") (pinfunction "2_2") (pintype "passive"))
      (node (ref "C82") (pin "2") (pinfunction "2_2") (pintype "passive"))
      (node (ref "C85") (pin "2") (pinfunction "2_2") (pintype "passive"))
      (node (ref "C88") (pin "2") (pinfunction "2_2") (pintype "passive"))
      (node (ref "C91") (pin "2") (pinfunction "2_2") (pintype "passive"))
      (node (ref "C94") (pin "2") (pinfunction "2_2") (pintype "passive"))
      (node (ref "C95") (pin "2") (pinfunction "2_2") (pintype "passive"))
      (node (ref "R121") (pin "1") (pinfunction "1_1") (pintype "passive"))
      (node (ref "U11") (pin "1") (pinfunction "-Vi_1") (pintype "power_in"))
      (node (ref "U12") (pin "4") (pinfunction "Gnd1_4") (pintype "power_in"))
      (node (ref "U13") (pin "4") (pinfunction "Gnd1_4") (pintype "power_in"))
      (node (ref "U16") (pin "4") (pinfunction "Gnd1_4") (pintype "power_in"))
      (node (ref "U17") (pin "4") (pinfunction "Gnd1_4") (pintype "power_in"))
      (node (ref "U20") (pin "1") (pinfunction "-Vi_1") (pintype "power_in"))
      (node (ref "U21") (pin "1") (pinfunction "-Vi_1") (pintype "power_in"))
      (node (ref "U8") (pin "1") (pinfunction "-Vi_1") (pintype "power_in"))
    )
    (net (code "18") (name "GND_1") (class "Default")
      (node (ref "C104") (pin "2") (pinfunction "2_2") (pintype "passive"))
      (node (ref "C105") (pin "2") (pinfunction "2_2") (pintype "passive"))
      (node (ref "C86") (pin "2") (pinfunction "2_2") (pintype "passive"))
      (node (ref "C89") (pin "2") (pinfunction "2_2") (pintype "passive"))
      (node (ref "C92") (pin "2") (pinfunction "2_2") (pintype "passive"))
      (node (ref "C98") (pin "2") (pinfunction "2_2") (pintype "passive"))
      (node (ref "L1") (pin "2") (pinfunction "2_2") (pintype "passive"))
      (node (ref "R87") (pin "1") (pinfunction "1_1") (pintype "passive"))
      (node (ref "U12") (pin "5") (pinfunction "Gnd2_5") (pintype "power_in"))
      (node (ref "U14") (pin "3") (pinfunction "GND_3") (pintype "power_in"))
      (node (ref "U14") (pin "EP") (pinfunction "EP_EP") (pintype "passive"))
      (node (ref "U9") (pin "2") (pinfunction "GND_2") (pintype "power_in"))
    )
    (net (code "19") (name "GND_2") (class "Default")
      (node (ref "C108") (pin "2") (pinfunction "2_2") (pintype "passive"))
      (node (ref "C114") (pin "2") (pinfunction "2_2") (pintype "passive"))
      (node (ref "C120") (pin "2") (pinfunction "2_2") (pintype "passive"))
      (node (ref "C121") (pin "2") (pinfunction "2_2") (pintype "passive"))
      (node (ref "C132") (pin "2") (pinfunction "2_2") (pintype "passive"))
      (node (ref "C135") (pin "2") (pinfunction "2_2") (pintype "passive"))
      (node (ref "L3") (pin "3") (pinfunction "3_3") (pintype "passive"))
      (node (ref "R122") (pin "1") (pinfunction "1_1") (pintype "passive"))
      (node (ref "U16") (pin "5") (pinfunction "Gnd2_5") (pintype "power_in"))
      (node (ref "U18") (pin "3") (pinfunction "GND_3") (pintype "power_in"))
      (node (ref "U18") (pin "EP") (pinfunction "EP_EP") (pintype "passive"))
      (node (ref "U22") (pin "2") (pinfunction "GND_2") (pintype "power_in"))
    )
    (net (code "20") (name "GND_3") (class "Default")
      (node (ref "C106") (pin "2") (pinfunction "2_2") (pintype "passive"))
      (node (ref "C107") (pin "2") (pinfunction "2_2") (pintype "passive"))
      (node (ref "C87") (pin "2") (pinfunction "2_2") (pintype "passive"))
      (node (ref "C90") (pin "2") (pinfunction "2_2") (pintype "passive"))
      (node (ref "C93") (pin "2") (pinfunction "2_2") (pintype "passive"))
      (node (ref "C99") (pin "2") (pinfunction "2_2") (pintype "passive"))
      (node (ref "L2") (pin "2") (pinfunction "2_2") (pintype "passive"))
      (node (ref "R88") (pin "1") (pinfunction "1_1") (pintype "passive"))
      (node (ref "U10") (pin "2") (pinfunction "GND_2") (pintype "power_in"))
      (node (ref "U13") (pin "5") (pinfunction "Gnd2_5") (pintype "power_in"))
      (node (ref "U15") (pin "3") (pinfunction "GND_3") (pintype "power_in"))
      (node (ref "U15") (pin "EP") (pinfunction "EP_EP") (pintype "passive"))
    )
    (net (code "21") (name "GND_4") (class "Default")
      (node (ref "C109") (pin "2") (pinfunction "2_2") (pintype "passive"))
      (node (ref "C115") (pin "2") (pinfunction "2_2") (pintype "passive"))
      (node (ref "C122") (pin "2") (pinfunction "2_2") (pintype "passive"))
      (node (ref "C123") (pin "2") (pinfunction "2_2") (pintype "passive"))
      (node (ref "C133") (pin "2") (pinfunction "2_2") (pintype "passive"))
      (node (ref "C136") (pin "2") (pinfunction "2_2") (pintype "passive"))
      (node (ref "L4") (pin "3") (pinfunction "3_3") (pintype "passive"))
      (node (ref "R123") (pin "1") (pinfunction "1_1") (pintype "passive"))
      (node (ref "U17") (pin "5") (pinfunction "Gnd2_5") (pintype "power_in"))
      (node (ref "U19") (pin "3") (pinfunction "GND_3") (pintype "power_in"))
      (node (ref "U19") (pin "EP") (pinfunction "EP_EP") (pintype "passive"))
      (node (ref "U23") (pin "2") (pinfunction "GND_2") (pintype "power_in"))
    )
    (net (code "22") (name "GND_HV") (class "Default")
      (node (ref "R118") (pin "1") (pinfunction "1_1") (pintype "passive"))
      (node (ref "R121") (pin "2") (pinfunction "2_2") (pintype "passive"))
      (node (ref "X11") (pin "1") (pinfunction "1_1") (pintype "passive"))
    )
    (net (code "23") (name "Net-(C96-Pad2)") (class "Default")
      (node (ref "C96") (pin "2") (pinfunction "2_2") (pintype "passive"))
      (node (ref "R100") (pin "2") (pinfunction "2_2") (pintype "passive"))
      (node (ref "R100A") (pin "2") (pinfunction "2_2") (pintype "passive"))
      (node (ref "R100B") (pin "2") (pinfunction "2_2") (pintype "passive"))
      (node (ref "R100C") (pin "2") (pinfunction "2_2") (pintype "passive"))
    )
    (net (code "24") (name "Net-(C97-Pad2)") (class "Default")
      (node (ref "C97") (pin "2") (pinfunction "2_2") (pintype "passive"))
      (node (ref "R101") (pin "2") (pinfunction "2_2") (pintype "passive"))
      (node (ref "R101A") (pin "2") (pinfunction "2_2") (pintype "passive"))
      (node (ref "R101B") (pin "2") (pinfunction "2_2") (pintype "passive"))
      (node (ref "R101C") (pin "2") (pinfunction "2_2") (pintype "passive"))
    )
    (net (code "25") (name "Net-(C112-Pad2)") (class "Default")
      (node (ref "C112") (pin "2") (pinfunction "2_2") (pintype "passive"))
      (node (ref "R114") (pin "2") (pinfunction "2_2") (pintype "passive"))
      (node (ref "R114A") (pin "2") (pinfunction "2_2") (pintype "passive"))
      (node (ref "R114B") (pin "2") (pinfunction "2_2") (pintype "passive"))
      (node (ref "R114C") (pin "2") (pinfunction "2_2") (pintype "passive"))
    )
    (net (code "26") (name "Net-(C113-Pad2)") (class "Default")
      (node (ref "C113") (pin "2") (pinfunction "2_2") (pintype "passive"))
      (node (ref "R115") (pin "2") (pinfunction "2_2") (pintype "passive"))
      (node (ref "R115A") (pin "2") (pinfunction "2_2") (pintype "passive"))
      (node (ref "R115B") (pin "2") (pinfunction "2_2") (pintype "passive"))
      (node (ref "R115C") (pin "2") (pinfunction "2_2") (pintype "passive"))
    )
    (net (code "27") (name "Net-(Q6-G)") (class "Default")
      (node (ref "D10") (pin "A") (pinfunction "A_A") (pintype "passive"))
      (node (ref "D12") (pin "A") (pinfunction "A_A") (pintype "passive"))
      (node (ref "Q6") (pin "1") (pinfunction "G_1") (pintype "passive"))
      (node (ref "Q7") (pin "1") (pinfunction "G_1") (pintype "passive"))
      (node (ref "R95") (pin "2") (pinfunction "2_2") (pintype "passive"))
      (node (ref "R95A") (pin "2") (pinfunction "2_2") (pintype "passive"))
      (node (ref "R97") (pin "2") (pinfunction "2_2") (pintype "passive"))
      (node (ref "R97A") (pin "2") (pinfunction "2_2") (pintype "passive"))
      (node (ref "R99") (pin "2") (pinfunction "2_2") (pintype "passive"))
    )
    (net (code "28") (name "Net-(Q8-G)") (class "Default")
      (node (ref "D11") (pin "A") (pinfunction "A_A") (pintype "passive"))
      (node (ref "D13") (pin "A") (pinfunction "A_A") (pintype "passive"))
      (node (ref "Q8") (pin "1") (pinfunction "G_1") (pintype "passive"))
      (node (ref "Q9") (pin "1") (pinfunction "G_1") (pintype "passive"))
      (node (ref "R102") (pin "2") (pinfunction "2_2") (pintype "passive"))
      (node (ref "R96") (pin "1") (pinfunction "1_1") (pintype "passive"))
      (node (ref "R96A") (pin "1") (pinfunction "1_1") (pintype "passive"))
      (node (ref "R98") (pin "1") (pinfunction "1_1") (pintype "passive"))
      (node (ref "R98A") (pin "1") (pinfunction "1_1") (pintype "passive"))
    )
    (net (code "29") (name "Net-(Q10-G)") (class "Default")
      (node (ref "D14") (pin "A") (pinfunction "A_A") (pintype "passive"))
      (node (ref "D16") (pin "A") (pinfunction "A_A") (pintype "passive"))
      (node (ref "Q10") (pin "1") (pinfunction "G_1") (pintype "passive"))
      (node (ref "Q11") (pin "1") (pinfunction "G_1") (pintype "passive"))
      (node (ref "R109") (pin "2") (pinfunction "2_2") (pintype "passive"))
      (node (ref "R109A") (pin "2") (pinfunction "2_2") (pintype "passive"))
      (node (ref "R111") (pin "2") (pinfunction "2_2") (pintype "passive"))
      (node (ref "R111A") (pin "2") (pinfunction "2_2") (pintype "passive"))
      (node (ref "R113") (pin "2") (pinfunction "2_2") (pintype "passive"))
    )
    (net (code "30") (name "Net-(Q12-G)") (class "Default")
      (node (ref "D15") (pin "A") (pinfunction "A_A") (pintype "passive"))
      (node (ref "D17") (pin "A") (pinfunction "A_A") (pintype "passive"))
      (node (ref "Q12") (pin "1") (pinfunction "G_1") (pintype "passive"))
      (node (ref "Q13") (pin "1") (pinfunction "G_1") (pintype "passive"))
      (node (ref "R110") (pin "1") (pinfunction "1_1") (pintype "passive"))
      (node (ref "R110A") (pin "1") (pinfunction "1_1") (pintype "passive"))
      (node (ref "R112") (pin "1") (pinfunction "1_1") (pintype "passive"))
      (node (ref "R112A") (pin "1") (pinfunction "1_1") (pintype "passive"))
      (node (ref "R116") (pin "2") (pinfunction "2_2") (pintype "passive"))
    )
    (net (code "31") (name "Net-(U8-+Vi)") (class "Default")
      (node (ref "C82") (pin "1") (pinfunction "1_1") (pintype "passive"))
      (node (ref "FB6") (pin "2") (pinfunction "2_2") (pintype "passive"))
      (node (ref "U8") (pin "2") (pinfunction "+Vi_2") (pintype "power_in"))
    )
    (net (code "32") (name "Net-(U8-+Vo)") (class "Default")
      (node (ref "C83") (pin "1") (pinfunction "1_1") (pintype "passive"))
      (node (ref "L1") (pin "4") (pinfunction "4_4") (pintype "passive"))
      (node (ref "U8") (pin "6") (pinfunction "+Vo_6") (pintype "power_in"))
    )
    (net (code "33") (name "Net-(U8--Vo)") (class "Default")
      (node (ref "C83") (pin "2") (pinfunction "2_2") (pintype "passive"))
      (node (ref "L1") (pin "1") (pinfunction "1_1") (pintype "passive"))
      (node (ref "U8") (pin "7") (pinfunction "-Vo_7") (pintype "power_in"))
    )
    (net (code "34") (name "Net-(U9-IN)") (class "Default")
      (node (ref "C86") (pin "1") (pinfunction "1_1") (pintype "passive"))
      (node (ref "FB7") (pin "2") (pinfunction "2_2") (pintype "passive"))
      (node (ref "U9") (pin "4") (pinfunction "IN_4") (pintype "power_in"))
    )
    (net (code "35") (name "Net-(U10-IN)") (class "Default")
      (node (ref "C87") (pin "1") (pinfunction "1_1") (pintype "passive"))
      (node (ref "FB8") (pin "2") (pinfunction "2_2") (pintype "passive"))
      (node (ref "U10") (pin "4") (pinfunction "IN_4") (pintype "power_in"))
    )
    (net (code "36") (name "Net-(U11-+Vi)") (class "Default")
      (node (ref "C85") (pin "1") (pinfunction "1_1") (pintype "passive"))
      (node (ref "FB9") (pin "2") (pinfunction "2_2") (pintype "passive"))
      (node (ref "U11") (pin "2") (pinfunction "+Vi_2") (pintype "power_in"))
    )
    (net (code "37") (name "Net-(U11-+Vo)") (class "Default")
      (node (ref "C84") (pin "1") (pinfunction "1_1") (pintype "passive"))
      (node (ref "L2") (pin "4") (pinfunction "4_4") (pintype "passive"))
      (node (ref "U11") (pin "6") (pinfunction "+Vo_6") (pintype "power_in"))
    )
    (net (code "38") (name "Net-(U11--Vo)") (class "Default")
      (node (ref "C84") (pin "2") (pinfunction "2_2") (pintype "passive"))
      (node (ref "L2") (pin "1") (pinfunction "1_1") (pintype "passive"))
      (node (ref "U11") (pin "7") (pinfunction "-Vo_7") (pintype "power_in"))
    )
    (net (code "39") (name "Net-(U12-A1)") (class "Default")
      (node (ref "R91") (pin "2") (pinfunction "2_2") (pintype "passive"))
      (node (ref "U12") (pin "2") (pinfunction "A1_2") (pintype "input"))
    )
    (net (code "40") (name "Net-(U12-B1)") (class "Default")
      (node (ref "TP8") (pin "1") (pinfunction "1_1") (pintype "passive"))
      (node (ref "U12") (pin "7") (pinfunction "B1_7") (pintype "output"))
    )
    (net (code "41") (name "Net-(U12-B2)") (class "Default")
      (node (ref "R93") (pin "1") (pinfunction "1_1") (pintype "passive"))
      (node (ref "U12") (pin "6") (pinfunction "B2_6") (pintype "output"))
    )
    (net (code "42") (name "Net-(U12-Vdd1)") (class "Default")
      (node (ref "C94") (pin "1") (pinfunction "1_1") (pintype "passive"))
      (node (ref "FB10") (pin "2") (pinfunction "2_2") (pintype "passive"))
      (node (ref "U12") (pin "1") (pinfunction "Vdd1_1") (pintype "power_in"))
    )
    (net (code "43") (name "Net-(U13-A1)") (class "Default")
      (node (ref "R92") (pin "2") (pinfunction "2_2") (pintype "passive"))
      (node (ref "U13") (pin "2") (pinfunction "A1_2") (pintype "input"))
    )
    (net (code "44") (name "Net-(U13-B1)") (class "Default")
      (node (ref "TP10") (pin "1") (pinfunction "1_1") (pintype "passive"))
      (node (ref "U13") (pin "7") (pinfunction "B1_7") (pintype "output"))
    )
    (net (code "45") (name "Net-(U13-B2)") (class "Default")
      (node (ref "R94") (pin "2") (pinfunction "2_2") (pintype "passive"))
      (node (ref "U13") (pin "6") (pinfunction "B2_6") (pintype "output"))
    )
    (net (code "46") (name "Net-(U13-Vdd1)") (class "Default")
      (node (ref "C95") (pin "1") (pinfunction "1_1") (pintype "passive"))
      (node (ref "FB11") (pin "2") (pinfunction "2_2") (pintype "passive"))
      (node (ref "U13") (pin "1") (pinfunction "Vdd1_1") (pintype "power_in"))
    )
    (net (code "47") (name "Net-(U14-EN)") (class "Default")
      (node (ref "R89") (pin "1") (pinfunction "1_1") (pintype "passive"))
      (node (ref "TP7") (pin "1") (pinfunction "1_1") (pintype "passive"))
      (node (ref "U14") (pin "5") (pinfunction "EN_5") (pintype "input"))
    )
    (net (code "48") (name "Net-(U14-IN)") (class "Default")
      (node (ref "C98") (pin "1") (pinfunction "1_1") (pintype "passive"))
      (node (ref "R93") (pin "2") (pinfunction "2_2") (pintype "passive"))
      (node (ref "U14") (pin "4") (pinfunction "IN_4") (pintype "input"))
    )
    (net (code "49") (name "Net-(U14-OUT)") (class "Default")
      (node (ref "D12") (pin "C") (pinfunction "C_C") (pintype "passive"))
      (node (ref "R95") (pin "1") (pinfunction "1_1") (pintype "passive"))
      (node (ref "R95A") (pin "1") (pinfunction "1_1") (pintype "passive"))
      (node (ref "R97") (pin "1") (pinfunction "1_1") (pintype "passive"))
      (node (ref "R97A") (pin "1") (pinfunction "1_1") (pintype "passive"))
      (node (ref "U14") (pin "2") (pinfunction "OUT_2") (pintype "output"))
    )
    (net (code "50") (name "Net-(U15-EN)") (class "Default")
      (node (ref "R90") (pin "2") (pinfunction "2_2") (pintype "passive"))
      (node (ref "TP9") (pin "1") (pinfunction "1_1") (pintype "passive"))
      (node (ref "U15") (pin "5") (pinfunction "EN_5") (pintype "input"))
    )
    (net (code "51") (name "Net-(U15-IN)") (class "Default")
      (node (ref "C99") (pin "1") (pinfunction "1_1") (pintype "passive"))
      (node (ref "R94") (pin "1") (pinfunction "1_1") (pintype "passive"))
      (node (ref "U15") (pin "4") (pinfunction "IN_4") (pintype "input"))
    )
    (net (code "52") (name "Net-(U15-OUT)") (class "Default")
      (node (ref "D13") (pin "C") (pinfunction "C_C") (pintype "passive"))
      (node (ref "R96") (pin "2") (pinfunction "2_2") (pintype "passive"))
      (node (ref "R96A") (pin "2") (pinfunction "2_2") (pintype "passive"))
      (node (ref "R98") (pin "2") (pinfunction "2_2") (pintype "passive"))
      (node (ref "R98A") (pin "2") (pinfunction "2_2") (pintype "passive"))
      (node (ref "U15") (pin "2") (pinfunction "OUT_2") (pintype "output"))
    )
    (net (code "53") (name "Net-(U16-A1)") (class "Default")
      (node (ref "R105") (pin "2") (pinfunction "2_2") (pintype "passive"))
      (node (ref "U16") (pin "2") (pinfunction "A1_2") (pintype "input"))
    )
    (net (code "54") (name "Net-(U16-B1)") (class "Default")
      (node (ref "TP11") (pin "1") (pinfunction "1_1") (pintype "passive"))
      (node (ref "U16") (pin "7") (pinfunction "B1_7") (pintype "output"))
    )
    (net (code "55") (name "Net-(U16-B2)") (class "Default")
      (node (ref "R107") (pin "1") (pinfunction "1_1") (pintype "passive"))
      (node (ref "U16") (pin "6") (pinfunction "B2_6") (pintype "output"))
    )
    (net (code "56") (name "Net-(U16-Vdd1)") (class "Default")
      (node (ref "C110") (pin "1") (pinfunction "1_1") (pintype "passive"))
      (node (ref "FB12") (pin "2") (pinfunction "2_2") (pintype "passive"))
      (node (ref "U16") (pin "1") (pinfunction "Vdd1_1") (pintype "power_in"))
    )
    (net (code "57") (name "Net-(U17-A1)") (class "Default")
      (node (ref "R106") (pin "2") (pinfunction "2_2") (pintype "passive"))
      (node (ref "U17") (pin "2") (pinfunction "A1_2") (pintype "input"))
    )
    (net (code "58") (name "Net-(U17-B1)") (class "Default")
      (node (ref "TP14") (pin "1") (pinfunction "1_1") (pintype "passive"))
      (node (ref "U17") (pin "7") (pinfunction "B1_7") (pintype "output"))
    )
    (net (code "59") (name "Net-(U17-B2)") (class "Default")
      (node (ref "R108") (pin "2") (pinfunction "2_2") (pintype "passive"))
      (node (ref "U17") (pin "6") (pinfunction "B2_6") (pintype "output"))
    )
    (net (code "60") (name "Net-(U17-Vdd1)") (class "Default")
      (node (ref "C111") (pin "1") (pinfunction "1_1") (pintype "passive"))
      (node (ref "FB13") (pin "2") (pinfunction "2_2") (pintype "passive"))
      (node (ref "U17") (pin "1") (pinfunction "Vdd1_1") (pintype "power_in"))
    )
    (net (code "61") (name "Net-(U18-EN)") (class "Default")
      (node (ref "R103") (pin "1") (pinfunction "1_1") (pintype "passive"))
      (node (ref "TP12") (pin "1") (pinfunction "1_1") (pintype "passive"))
      (node (ref "U18") (pin "5") (pinfunction "EN_5") (pintype "input"))
    )
    (net (code "62") (name "Net-(U18-IN)") (class "Default")
      (node (ref "C114") (pin "1") (pinfunction "1_1") (pintype "passive"))
      (node (ref "R107") (pin "2") (pinfunction "2_2") (pintype "passive"))
      (node (ref "U18") (pin "4") (pinfunction "IN_4") (pintype "input"))
    )
    (net (code "63") (name "Net-(U18-OUT)") (class "Default")
      (node (ref "D16") (pin "C") (pinfunction "C_C") (pintype "passive"))
      (node (ref "R109") (pin "1") (pinfunction "1_1") (pintype "passive"))
      (node (ref "R109A") (pin "1") (pinfunction "1_1") (pintype "passive"))
      (node (ref "R111") (pin "1") (pinfunction "1_1") (pintype "passive"))
      (node (ref "R111A") (pin "1") (pinfunction "1_1") (pintype "passive"))
      (node (ref "U18") (pin "2") (pinfunction "OUT_2") (pintype "output"))
    )
    (net (code "64") (name "Net-(U19-EN)") (class "Default")
      (node (ref "R104") (pin "2") (pinfunction "2_2") (pintype "passive"))
      (node (ref "TP13") (pin "1") (pinfunction "1_1") (pintype "passive"))
      (node (ref "U19") (pin "5") (pinfunction "EN_5") (pintype "input"))
    )
    (net (code "65") (name "Net-(U19-IN)") (class "Default")
      (node (ref "C115") (pin "1") (pinfunction "1_1") (pintype "passive"))
      (node (ref "R108") (pin "1") (pinfunction "1_1") (pintype "passive"))
      (node (ref "U19") (pin "4") (pinfunction "IN_4") (pintype "input"))
    )
    (net (code "66") (name "Net-(U19-OUT)") (class "Default")
      (node (ref "D17") (pin "C") (pinfunction "C_C") (pintype "passive"))
      (node (ref "R110") (pin "2") (pinfunction "2_2") (pintype "passive"))
      (node (ref "R110A") (pin "2") (pinfunction "2_2") (pintype "passive"))
      (node (ref "R112") (pin "2") (pinfunction "2_2") (pintype "passive"))
      (node (ref "R112A") (pin "2") (pinfunction "2_2") (pintype "passive"))
      (node (ref "U19") (pin "2") (pinfunction "OUT_2") (pintype "output"))
    )
    (net (code "67") (name "Net-(U20-+Vi)") (class "Default")
      (node (ref "C127") (pin "1") (pinfunction "1_1") (pintype "passive"))
      (node (ref "FB14") (pin "2") (pinfunction "2_2") (pintype "passive"))
      (node (ref "U20") (pin "2") (pinfunction "+Vi_2") (pintype "power_in"))
    )
    (net (code "68") (name "Net-(U20-+Vo)") (class "Default")
      (node (ref "C128") (pin "1") (pinfunction "1_1") (pintype "passive"))
      (node (ref "L3") (pin "1") (pinfunction "1_1") (pintype "passive"))
      (node (ref "U20") (pin "6") (pinfunction "+Vo_6") (pintype "power_in"))
    )
    (net (code "69") (name "Net-(U20--Vo)") (class "Default")
      (node (ref "C128") (pin "2") (pinfunction "2_2") (pintype "passive"))
      (node (ref "L3") (pin "4") (pinfunction "4_4") (pintype "passive"))
      (node (ref "U20") (pin "7") (pinfunction "-Vo_7") (pintype "power_in"))
    )
    (net (code "70") (name "Net-(U21-+Vi)") (class "Default")
      (node (ref "C130") (pin "1") (pinfunction "1_1") (pintype "passive"))
      (node (ref "FB15") (pin "2") (pinfunction "2_2") (pintype "passive"))
      (node (ref "U21") (pin "2") (pinfunction "+Vi_2") (pintype "power_in"))
    )
    (net (code "71") (name "Net-(U21-+Vo)") (class "Default")
      (node (ref "C129") (pin "1") (pinfunction "1_1") (pintype "passive"))
      (node (ref "L4") (pin "1") (pinfunction "1_1") (pintype "passive"))
      (node (ref "U21") (pin "6") (pinfunction "+Vo_6") (pintype "power_in"))
    )
    (net (code "72") (name "Net-(U21--Vo)") (class "Default")
      (node (ref "C129") (pin "2") (pinfunction "2_2") (pintype "passive"))
      (node (ref "L4") (pin "4") (pinfunction "4_4") (pintype "passive"))
      (node (ref "U21") (pin "7") (pinfunction "-Vo_7") (pintype "power_in"))
    )
    (net (code "73") (name "Net-(U22-IN)") (class "Default")
      (node (ref "C135") (pin "1") (pinfunction "1_1") (pintype "passive"))
      (node (ref "FB16") (pin "2") (pinfunction "2_2") (pintype "passive"))
      (node (ref "U22") (pin "4") (pinfunction "IN_4") (pintype "power_in"))
    )
    (net (code "74") (name "Net-(U23-IN)") (class "Default")
      (node (ref "C136") (pin "1") (pinfunction "1_1") (pintype "passive"))
      (node (ref "FB17") (pin "2") (pinfunction "2_2") (pintype "passive"))
      (node (ref "U23") (pin "4") (pinfunction "IN_4") (pintype "power_in"))
    )
    (net (code "75") (name "PWM_HL") (class "Default")
      (node (ref "U12") (pin "3") (pinfunction "A2_3") (pintype "input"))
    )
    (net (code "76") (name "PWM_HR") (class "Default")
      (node (ref "U13") (pin "3") (pinfunction "A2_3") (pintype "input"))
    )
    (net (code "77") (name "PWM_LL") (class "Default")
      (node (ref "U16") (pin "3") (pinfunction "A2_3") (pintype "input"))
    )
    (net (code "78") (name "PWM_LR") (class "Default")
      (node (ref "U17") (pin "3") (pinfunction "A2_3") (pintype "input"))
    )
    (net (code "79") (name "unconnected-(U8-NC-Pad14)") (class "Default")
      (node (ref "U8") (pin "14") (pinfunction "NC_14") (pintype "passive"))
    )
    (net (code "80") (name "unconnected-(U8-Off-Pad3)") (class "Default")
      (node (ref "U8") (pin "3") (pinfunction "Off_3") (pintype "power_in+no_connect"))
    )
    (net (code "81") (name "unconnected-(U9-NC-Pad1)") (class "Default")
      (node (ref "U9") (pin "1") (pinfunction "NC_1") (pintype "passive+no_connect"))
    )
    (net (code "82") (name "unconnected-(U9-NC-Pad3)") (class "Default")
      (node (ref "U9") (pin "3") (pinfunction "NC_3") (pintype "passive+no_connect"))
    )
    (net (code "83") (name "unconnected-(U10-NC-Pad1)") (class "Default")
      (node (ref "U10") (pin "1") (pinfunction "NC_1") (pintype "passive+no_connect"))
    )
    (net (code "84") (name "unconnected-(U10-NC-Pad3)") (class "Default")
      (node (ref "U10") (pin "3") (pinfunction "NC_3") (pintype "passive+no_connect"))
    )
    (net (code "85") (name "unconnected-(U11-NC-Pad14)") (class "Default")
      (node (ref "U11") (pin "14") (pinfunction "NC_14") (pintype "passive"))
    )
    (net (code "86") (name "unconnected-(U11-Off-Pad3)") (class "Default")
      (node (ref "U11") (pin "3") (pinfunction "Off_3") (pintype "power_in+no_connect"))
    )
    (net (code "87") (name "unconnected-(U20-NC-Pad14)") (class "Default")
      (node (ref "U20") (pin "14") (pinfunction "NC_14") (pintype "passive"))
    )
    (net (code "88") (name "unconnected-(U20-Off-Pad3)") (class "Default")
      (node (ref "U20") (pin "3") (pinfunction "Off_3") (pintype "power_in+no_connect"))
    )
    (net (code "89") (name "unconnected-(U21-NC-Pad14)") (class "Default")
      (node (ref "U21") (pin "14") (pinfunction "NC_14") (pintype "passive"))
    )
    (net (code "90") (name "unconnected-(U21-Off-Pad3)") (class "Default")
      (node (ref "U21") (pin "3") (pinfunction "Off_3") (pintype "power_in+no_connect"))
    )
    (net (code "91") (name "unconnected-(U22-NC-Pad1)") (class "Default")
      (node (ref "U22") (pin "1") (pinfunction "NC_1") (pintype "passive+no_connect"))
    )
    (net (code "92") (name "unconnected-(U22-NC-Pad3)") (class "Default")
      (node (ref "U22") (pin "3") (pinfunction "NC_3") (pintype "passive+no_connect"))
    )
    (net (code "93") (name "unconnected-(U23-NC-Pad1)") (class "Default")
      (node (ref "U23") (pin "1") (pinfunction "NC_1") (pintype "passive+no_connect"))
    )
    (net (code "94") (name "unconnected-(U23-NC-Pad3)") (class "Default")
      (node (ref "U23") (pin "3") (pinfunction "NC_3") (pintype "passive+no_connect"))
    )
  )
)
